# rekick2015-Prototyp.net
KiCad netlist of a schematic drawn in EAGLE
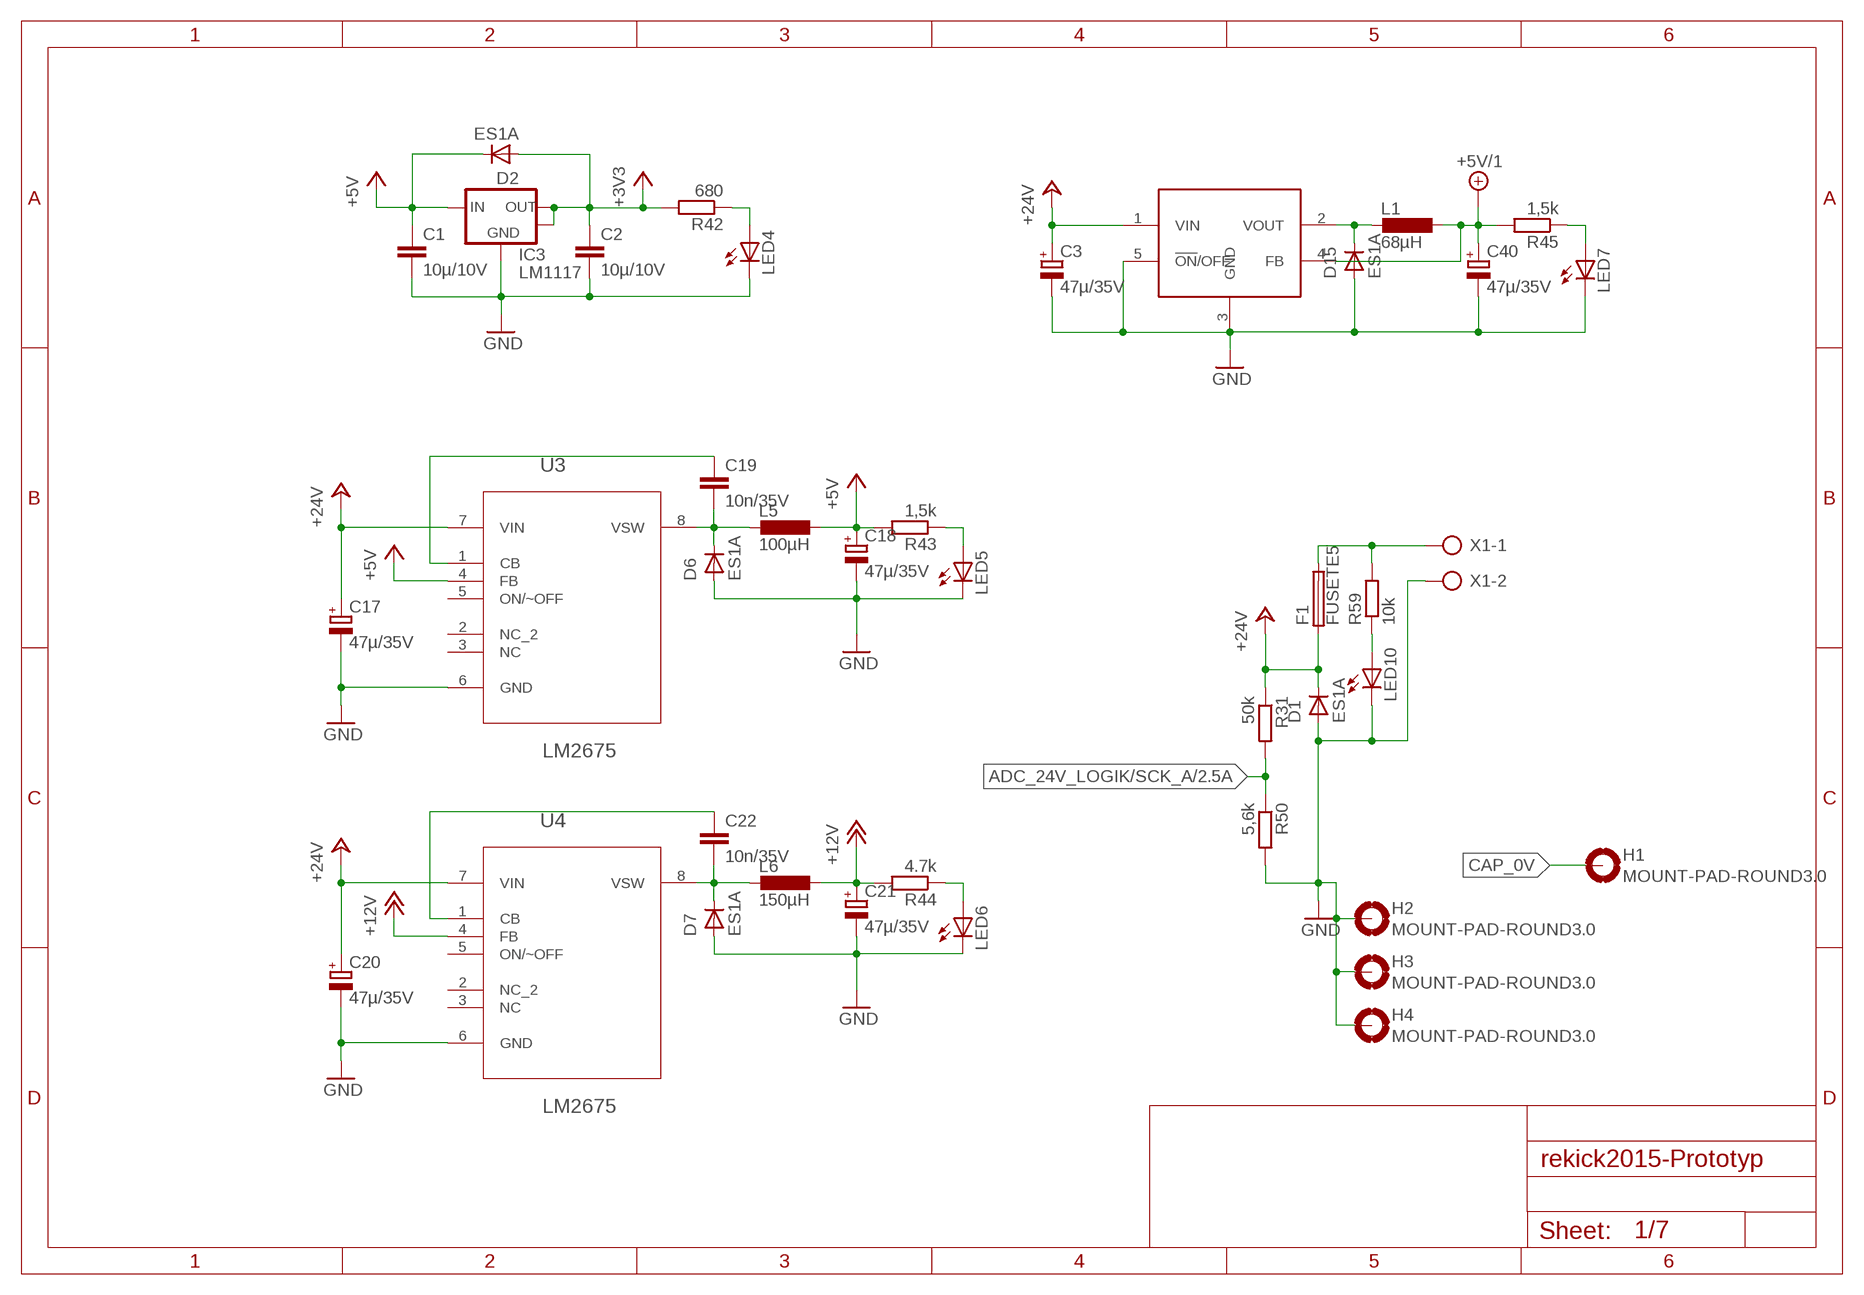
[diagram p0: schematic, sheet 1]
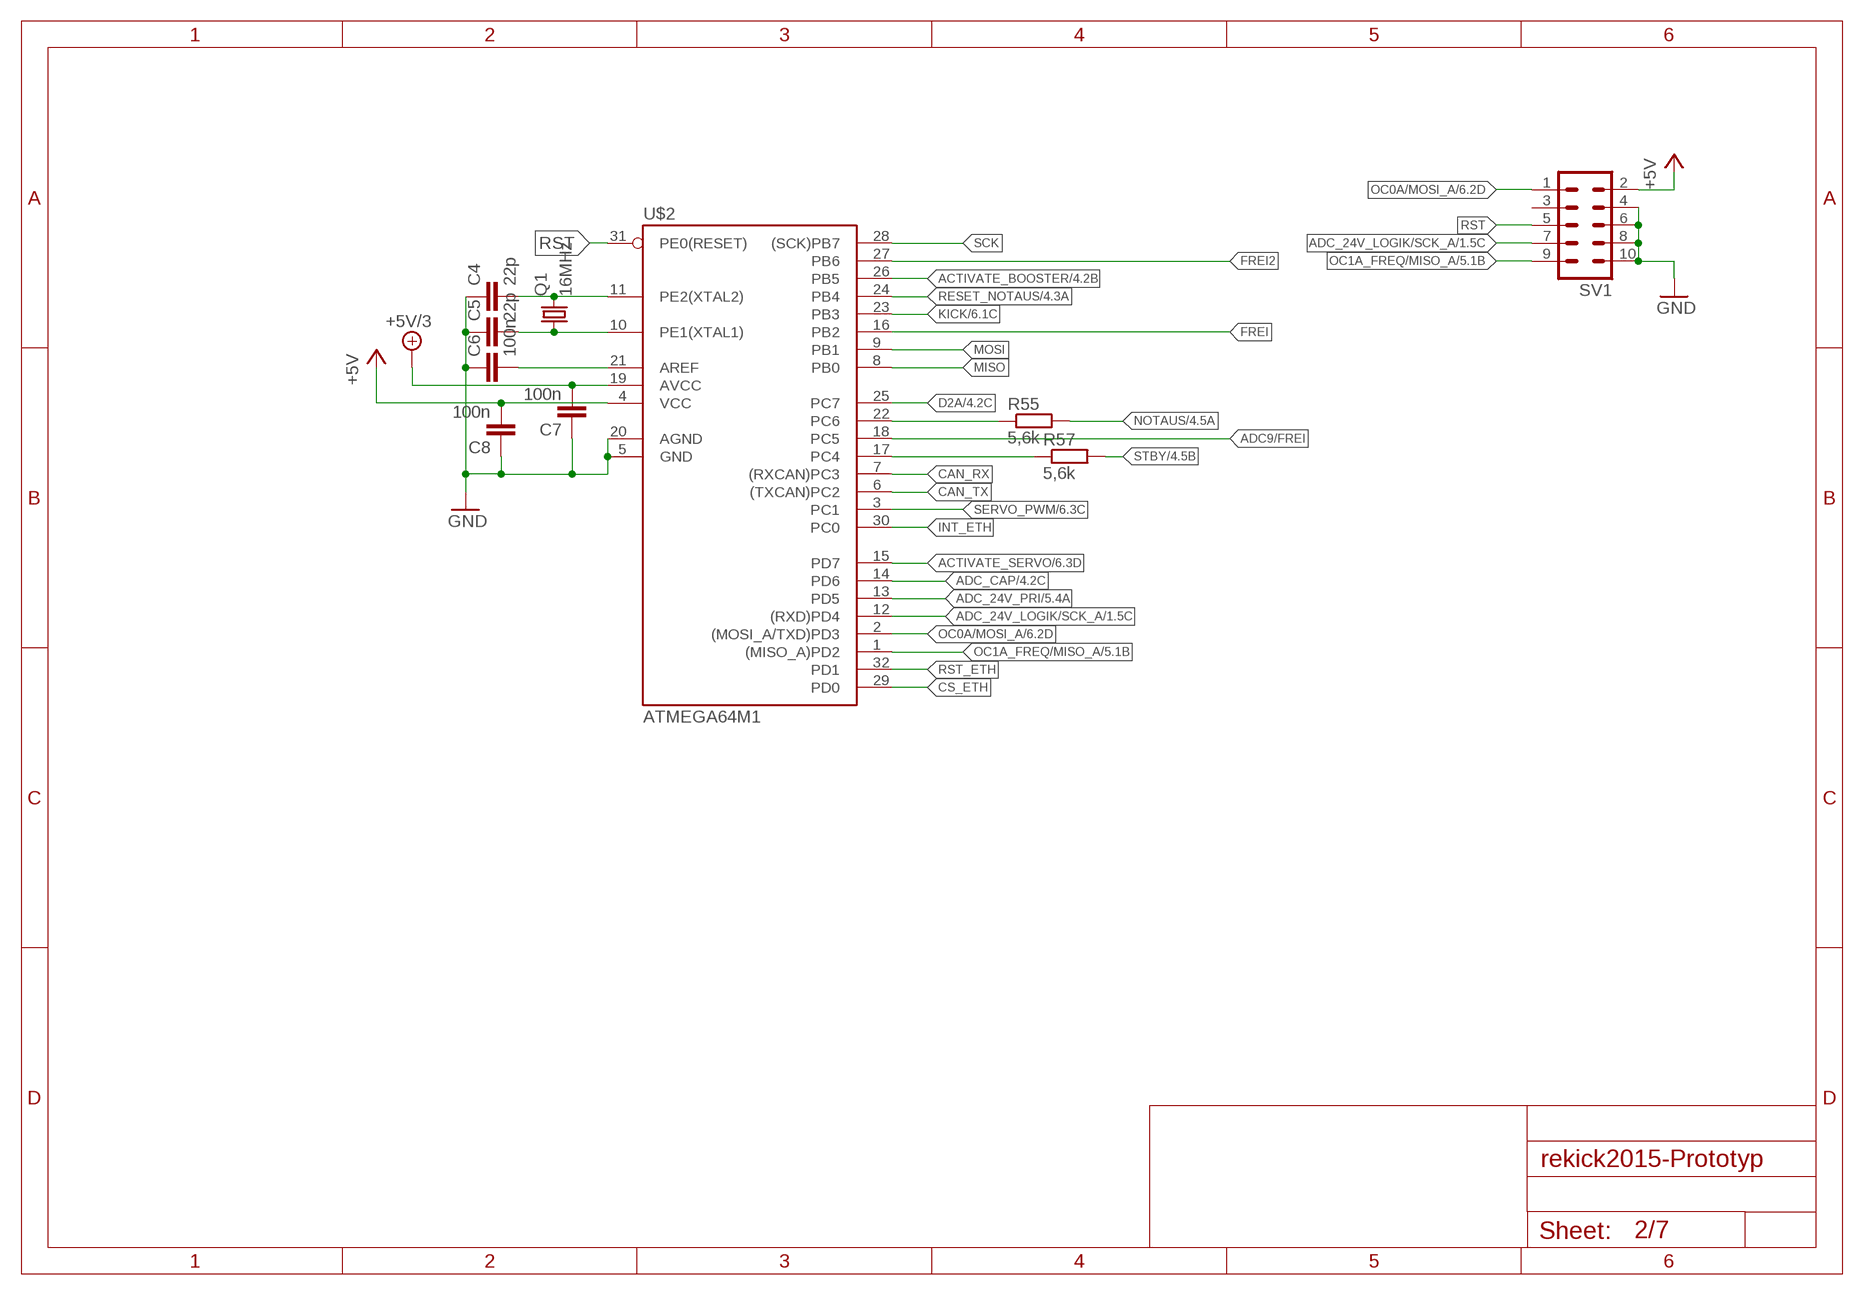
[diagram p1: schematic, sheet 2]
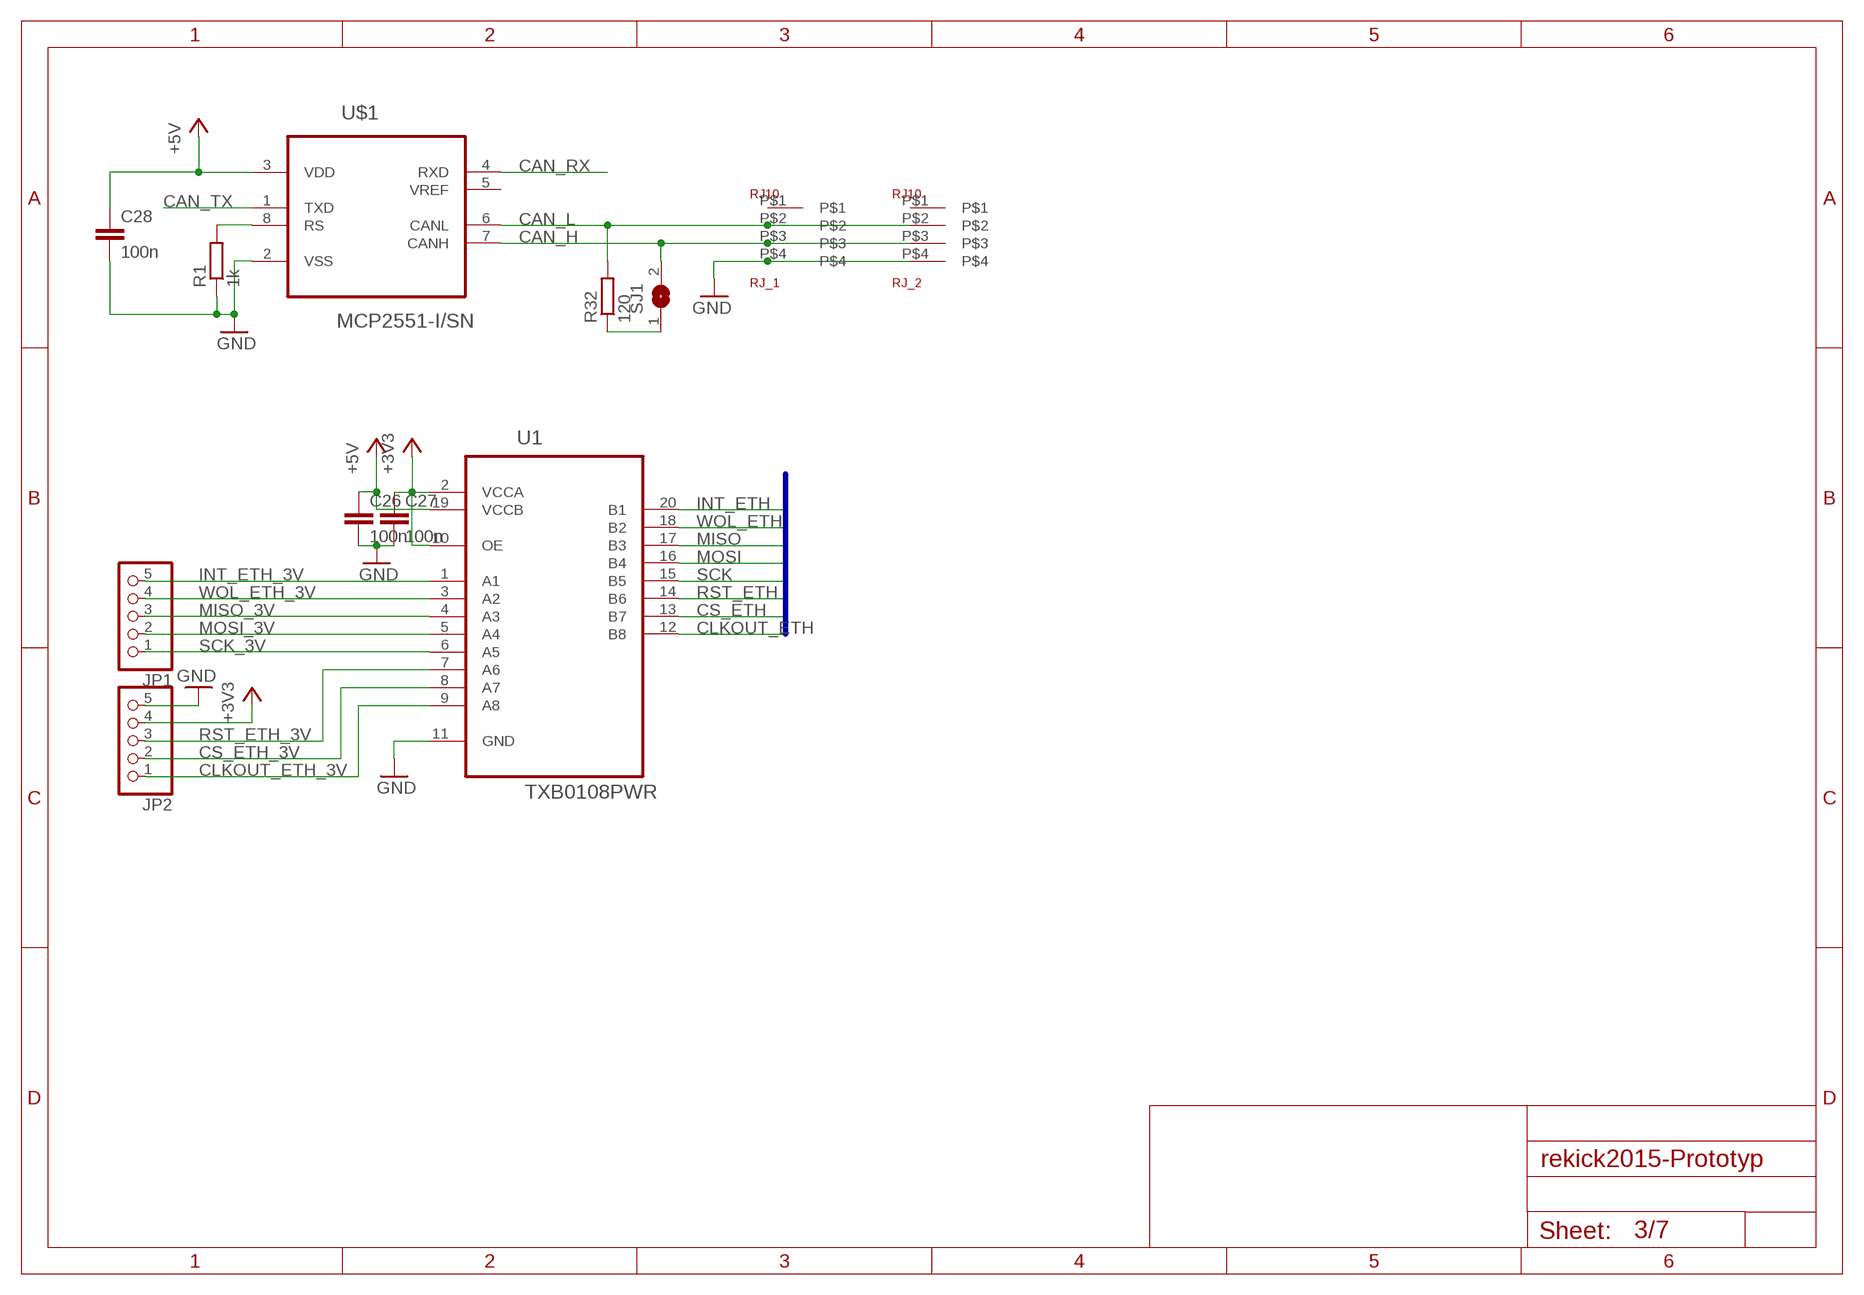
[diagram p2: schematic, sheet 3]
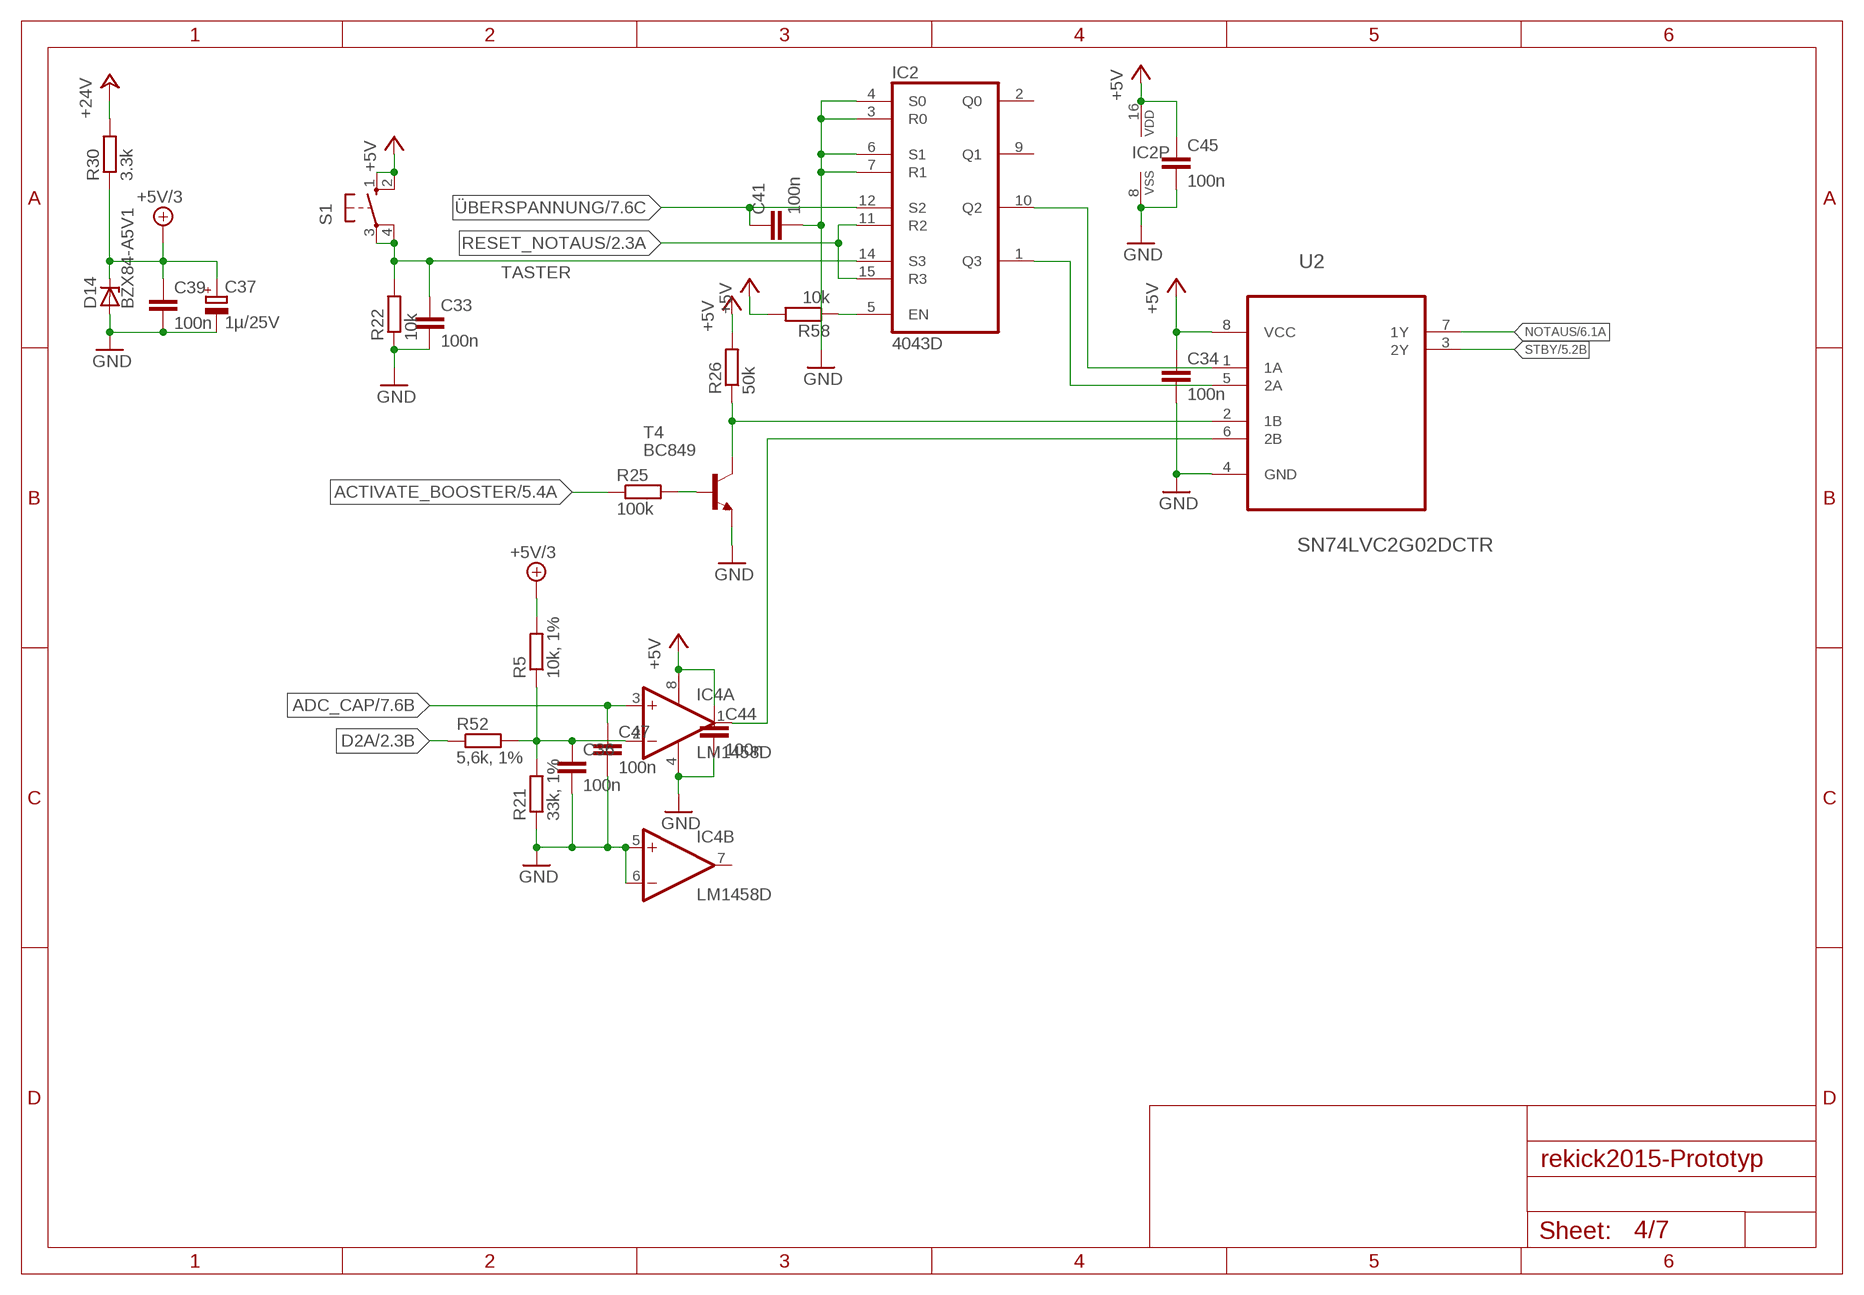
[diagram p3: schematic, sheet 4]
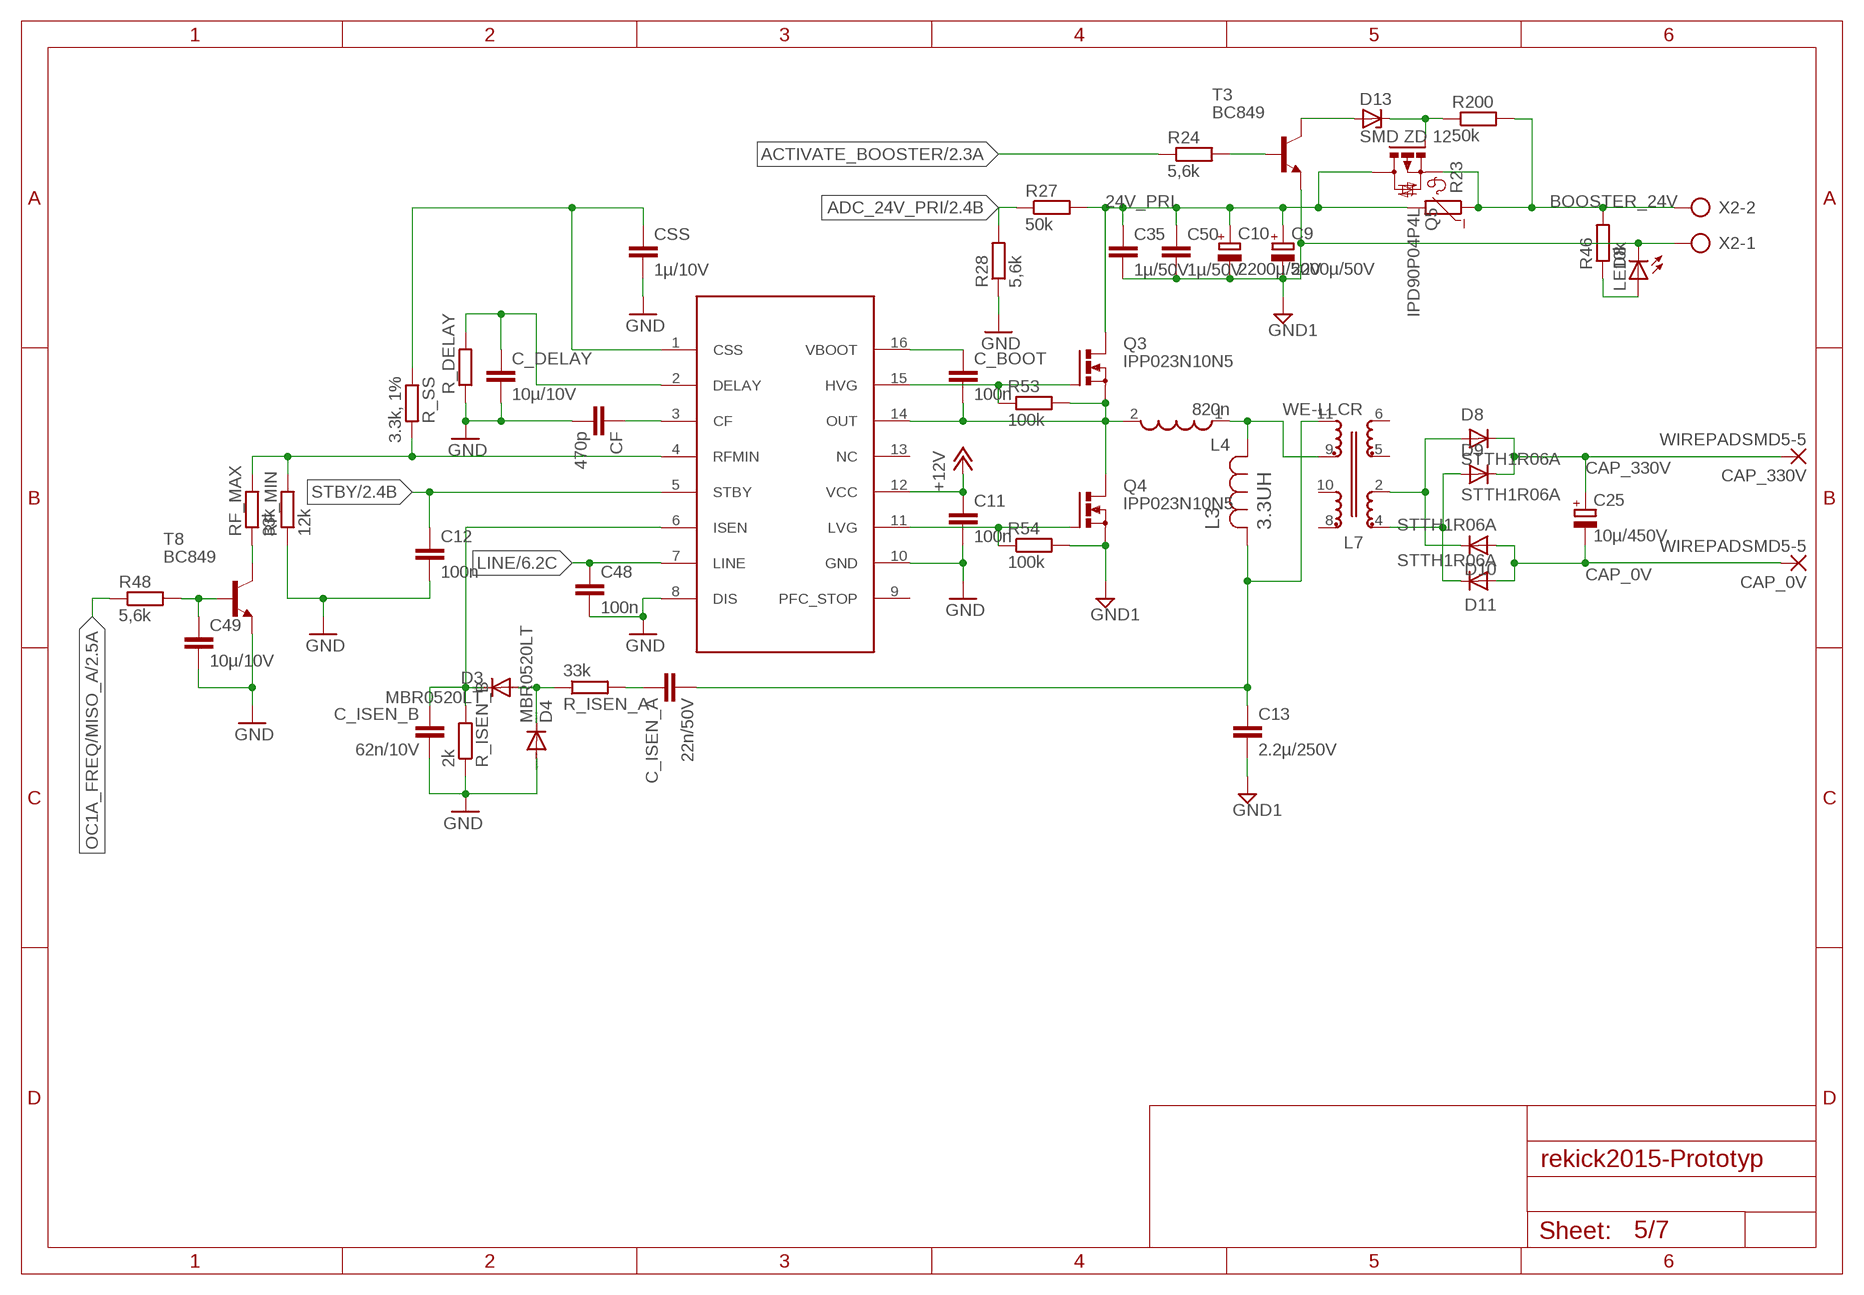
[diagram p4: schematic, sheet 5]
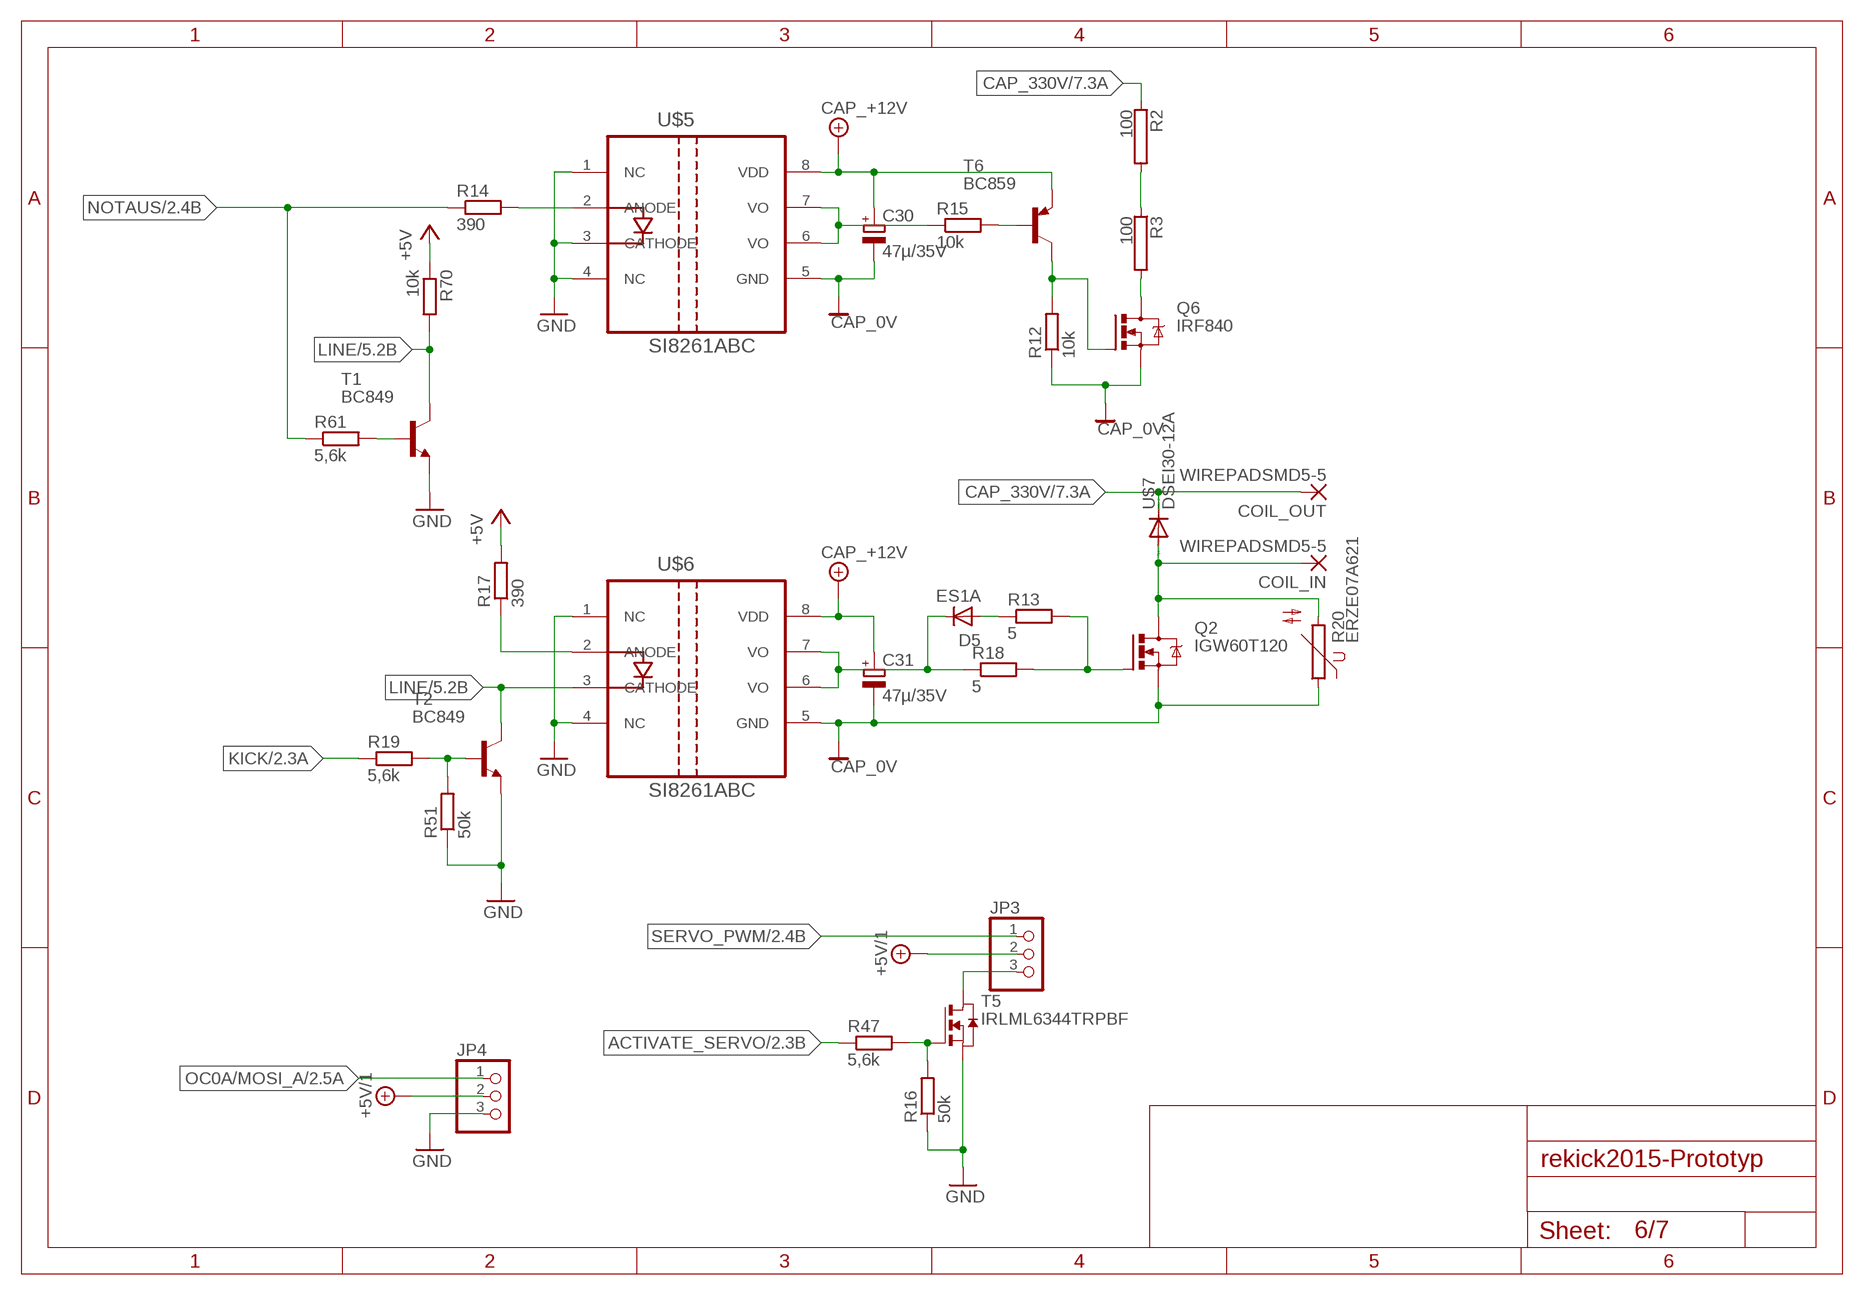
[diagram p5: schematic, sheet 6]
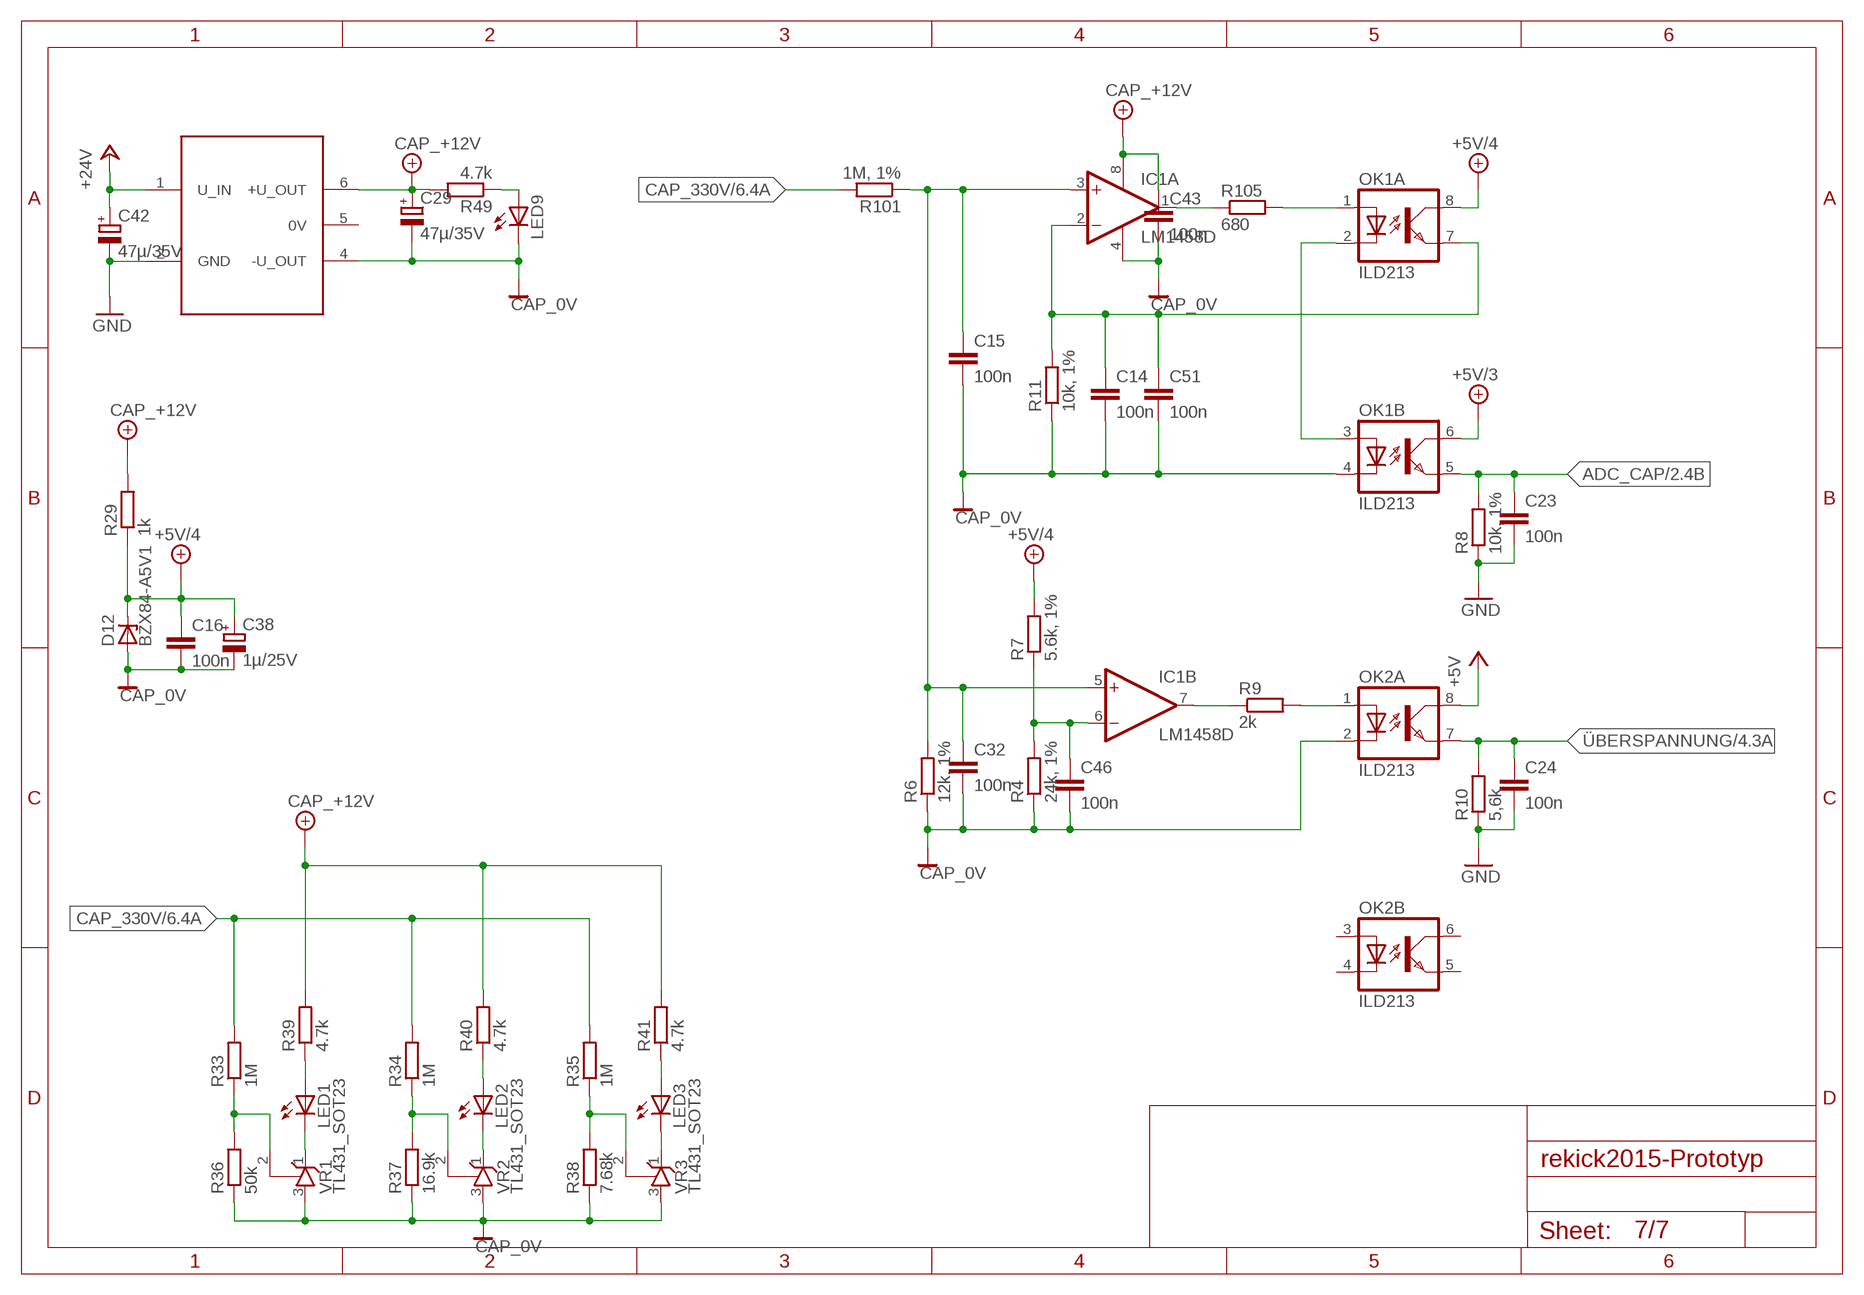
[diagram p6: schematic, sheet 7]

(export (version "E")
  (design (tool "Eeschema 10.0.6"))
  (components
    (comp (ref "C30")
      (value "47µ/35V")
      (footprint "eagle-import:E2-5")
      (libsource (lib "eagle-import") (part "CPOL-EUE2-5"))
    )
    (comp (ref "C31")
      (value "47µ/35V")
      (footprint "eagle-import:E2-5")
      (libsource (lib "eagle-import") (part "CPOL-EUE2-5"))
    )
    (comp (ref "COIL_IN")
      (value "WIREPADSMD5-5")
      (footprint "eagle-import:5-5")
      (libsource (lib "eagle-import") (part "WIREPADSMD5-5"))
    )
    (comp (ref "COIL_OUT")
      (value "WIREPADSMD5-5")
      (footprint "eagle-import:5-5")
      (libsource (lib "eagle-import") (part "WIREPADSMD5-5"))
    )
    (comp (ref "D5")
      (value "ES1A")
      (footprint "eagle-import:SMA-DO214AC")
      (libsource (lib "eagle-import") (part "GF1"))
    )
    (comp (ref "JP3")
      (value "PINHD-1X3")
      (footprint "eagle-import:1X03")
      (libsource (lib "eagle-import") (part "PINHD-1X3"))
    )
    (comp (ref "JP4")
      (value "PINHD-1X3")
      (footprint "eagle-import:1X03")
      (libsource (lib "eagle-import") (part "PINHD-1X3"))
    )
    (comp (ref "Q2")
      (value "IGW60T120")
      (footprint "eagle-import:TO247BV")
      (libsource (lib "eagle-import") (part "IRFPC40"))
    )
    (comp (ref "Q6")
      (value "IRF840")
      (footprint "eagle-import:TO220BV")
      (libsource (lib "eagle-import") (part "IRF740"))
    )
    (comp (ref "R2")
      (value "100")
      (footprint "eagle-import:HS25")
      (libsource (lib "eagle-import") (part "RHS25"))
    )
    (comp (ref "R3")
      (value "100")
      (footprint "eagle-import:HS25")
      (libsource (lib "eagle-import") (part "RHS25"))
    )
    (comp (ref "R12")
      (value "10k")
      (footprint "eagle-import:R0805")
      (libsource (lib "eagle-import") (part "R-EU_R0805"))
    )
    (comp (ref "R13")
      (value "5")
      (footprint "eagle-import:R2512")
      (libsource (lib "eagle-import") (part "R-EU_R2512"))
    )
    (comp (ref "R14")
      (value "390")
      (footprint "eagle-import:R0805")
      (libsource (lib "eagle-import") (part "R-EU_R0805"))
    )
    (comp (ref "R15")
      (value "10k")
      (footprint "eagle-import:R0805")
      (libsource (lib "eagle-import") (part "R-EU_R0805"))
    )
    (comp (ref "R16")
      (value "50k")
      (footprint "eagle-import:R0805")
      (libsource (lib "eagle-import") (part "R-EU_R0805"))
    )
    (comp (ref "R17")
      (value "390")
      (footprint "eagle-import:R0805")
      (libsource (lib "eagle-import") (part "R-EU_R0805"))
    )
    (comp (ref "R18")
      (value "5")
      (footprint "eagle-import:R2512")
      (libsource (lib "eagle-import") (part "R-EU_R2512"))
    )
    (comp (ref "R19")
      (value "5,6k")
      (footprint "eagle-import:R0805")
      (libsource (lib "eagle-import") (part "R-EU_R0805"))
    )
    (comp (ref "R20")
      (value "ERZE07A621")
      (footprint "eagle-import:S10K385")
      (libsource (lib "eagle-import") (part "S10K385"))
    )
    (comp (ref "R47")
      (value "5,6k")
      (footprint "eagle-import:R0805")
      (libsource (lib "eagle-import") (part "R-EU_R0805"))
    )
    (comp (ref "R51")
      (value "50k")
      (footprint "eagle-import:R0805")
      (libsource (lib "eagle-import") (part "R-EU_R0805"))
    )
    (comp (ref "R61")
      (value "5,6k")
      (footprint "eagle-import:R0805")
      (libsource (lib "eagle-import") (part "R-EU_R0805"))
    )
    (comp (ref "R70")
      (value "10k")
      (footprint "eagle-import:R0805")
      (libsource (lib "eagle-import") (part "R-EU_R0805"))
    )
    (comp (ref "T1")
      (value "BC849")
      (footprint "eagle-import:SOT23")
      (libsource (lib "eagle-import") (part "BC849"))
    )
    (comp (ref "T2")
      (value "BC849")
      (footprint "eagle-import:SOT23")
      (libsource (lib "eagle-import") (part "BC849"))
    )
    (comp (ref "T5")
      (value "IRLML6344TRPBF")
      (footprint "eagle-import:SOT-23")
      (libsource (lib "eagle-import") (part "NMOSSOT23"))
    )
    (comp (ref "T6")
      (value "BC859")
      (footprint "eagle-import:SOT23-BEC")
      (libsource (lib "eagle-import") (part "-PNP-SOT23-BECBC858C"))
    )
    (comp (ref "U$5")
      (value "SI8261ABC")
      (footprint "eagle-import:SOIC-8")
      (libsource (lib "eagle-import") (part "SI8261ABC"))
    )
    (comp (ref "U$6")
      (value "SI8261ABC")
      (footprint "eagle-import:SOIC-8")
      (libsource (lib "eagle-import") (part "SI8261ABC"))
    )
    (comp (ref "U$7")
      (value "DSEI30-12A")
      (footprint "eagle-import:TO247AD")
      (libsource (lib "eagle-import") (part "DSEI30-12A"))
    )
    (comp (ref "C33")
      (value "100n")
      (footprint "eagle-import:C0603")
      (libsource (lib "eagle-import") (part "C-EUC0603"))
    )
    (comp (ref "C34")
      (value "100n")
      (footprint "eagle-import:C0603")
      (libsource (lib "eagle-import") (part "C-EUC0603"))
    )
    (comp (ref "C36")
      (value "100n")
      (footprint "eagle-import:C0603")
      (libsource (lib "eagle-import") (part "C-EUC0603"))
    )
    (comp (ref "C37")
      (value "1µ/25V")
      (footprint "eagle-import:SMC_A")
      (libsource (lib "eagle-import") (part "CPOL-EUSMCA"))
    )
    (comp (ref "C39")
      (value "100n")
      (footprint "eagle-import:C0603")
      (libsource (lib "eagle-import") (part "C-EUC0603"))
    )
    (comp (ref "C41")
      (value "100n")
      (footprint "eagle-import:C0603")
      (libsource (lib "eagle-import") (part "C-EUC0603"))
    )
    (comp (ref "C44")
      (value "100n")
      (footprint "eagle-import:C0603")
      (libsource (lib "eagle-import") (part "C-EUC0603"))
    )
    (comp (ref "C45")
      (value "100n")
      (footprint "eagle-import:C0603")
      (libsource (lib "eagle-import") (part "C-EUC0603"))
    )
    (comp (ref "C47")
      (value "100n")
      (footprint "eagle-import:C0603")
      (libsource (lib "eagle-import") (part "C-EUC0603"))
    )
    (comp (ref "D14")
      (value "BZX84-A5V1")
      (footprint "eagle-import:TO236")
      (libsource (lib "eagle-import") (part "BZX84CSMD"))
    )
    (comp (ref "IC2")
      (value "4043D")
      (footprint "eagle-import:SO16")
      (libsource (lib "eagle-import") (part "4043D"))
    )
    (comp (ref "IC4")
      (value "LM1458D")
      (footprint "eagle-import:SO08")
      (libsource (lib "eagle-import") (part "1458DLM"))
    )
    (comp (ref "R5")
      (value "10k, 1%")
      (footprint "eagle-import:R0805")
      (libsource (lib "eagle-import") (part "R-EU_R0805"))
    )
    (comp (ref "R21")
      (value "33k, 1%")
      (footprint "eagle-import:R0805")
      (libsource (lib "eagle-import") (part "R-EU_R0805"))
    )
    (comp (ref "R22")
      (value "10k")
      (footprint "eagle-import:R0805")
      (libsource (lib "eagle-import") (part "R-EU_R0805"))
    )
    (comp (ref "R25")
      (value "100k")
      (footprint "eagle-import:R0805")
      (libsource (lib "eagle-import") (part "R-EU_R0805"))
    )
    (comp (ref "R26")
      (value "50k")
      (footprint "eagle-import:R0805")
      (libsource (lib "eagle-import") (part "R-EU_R0805"))
    )
    (comp (ref "R30")
      (value "3.3k")
      (footprint "eagle-import:R0805")
      (libsource (lib "eagle-import") (part "R-EU_R0805"))
    )
    (comp (ref "R52")
      (value "5,6k, 1%")
      (footprint "eagle-import:R0805")
      (libsource (lib "eagle-import") (part "R-EU_R0805"))
    )
    (comp (ref "R58")
      (value "10k")
      (footprint "eagle-import:R0805")
      (libsource (lib "eagle-import") (part "R-EU_R0805"))
    )
    (comp (ref "S1")
      (value "10-XX")
      (footprint "eagle-import:B3F-10XX")
      (libsource (lib "eagle-import") (part "10-XX"))
    )
    (comp (ref "T4")
      (value "BC849")
      (footprint "eagle-import:SOT23")
      (libsource (lib "eagle-import") (part "BC849"))
    )
    (comp (ref "U2")
      (value "SN74LVC2G02DCTR")
      (footprint "eagle-import:SOP65P400X130-8N")
      (libsource (lib "eagle-import") (part "SN74LVC2G02DCTR"))
    )
    (comp (ref "C9")
      (value "2200µ/50V")
      (footprint "eagle-import:E5-13")
      (libsource (lib "eagle-import") (part "CPOL-EUE5-13"))
    )
    (comp (ref "C10")
      (value "2200µ/50V")
      (footprint "eagle-import:E5-13")
      (libsource (lib "eagle-import") (part "CPOL-EUE5-13"))
    )
    (comp (ref "C11")
      (value "100n")
      (footprint "eagle-import:C0603")
      (libsource (lib "eagle-import") (part "C-EUC0603"))
    )
    (comp (ref "C12")
      (value "100n")
      (footprint "eagle-import:C0603")
      (libsource (lib "eagle-import") (part "C-EUC0603"))
    )
    (comp (ref "C13")
      (value "2.2µ/250V")
      (footprint "eagle-import:C2220K")
      (libsource (lib "eagle-import") (part "C-EUC2220K"))
    )
    (comp (ref "C25")
      (value "10µ/450V")
      (footprint "eagle-import:E5-10,5")
      (libsource (lib "eagle-import") (part "CPOL-EUE5-10.5"))
    )
    (comp (ref "C35")
      (value "1µ/50V")
      (footprint "eagle-import:C1206")
      (libsource (lib "eagle-import") (part "C-EUC1206"))
    )
    (comp (ref "C48")
      (value "100n")
      (footprint "eagle-import:C0603")
      (libsource (lib "eagle-import") (part "C-EUC0603"))
    )
    (comp (ref "C49")
      (value "10µ/10V")
      (footprint "eagle-import:C0603")
      (libsource (lib "eagle-import") (part "C-EUC0603"))
    )
    (comp (ref "C50")
      (value "1µ/50V")
      (footprint "eagle-import:C1206")
      (libsource (lib "eagle-import") (part "C-EUC1206"))
    )
    (comp (ref "CAP_0V")
      (value "WIREPADSMD5-5")
      (footprint "eagle-import:5-5")
      (libsource (lib "eagle-import") (part "WIREPADSMD5-5"))
    )
    (comp (ref "CAP_330V")
      (value "WIREPADSMD5-5")
      (footprint "eagle-import:5-5")
      (libsource (lib "eagle-import") (part "WIREPADSMD5-5"))
    )
    (comp (ref "CF")
      (value "470p")
      (footprint "eagle-import:C0603")
      (libsource (lib "eagle-import") (part "C-EUC0603"))
    )
    (comp (ref "CSS")
      (value "1µ/10V")
      (footprint "eagle-import:C0603")
      (libsource (lib "eagle-import") (part "C-EUC0603"))
    )
    (comp (ref "C_BOOT")
      (value "100n")
      (footprint "eagle-import:C0603")
      (libsource (lib "eagle-import") (part "C-EUC0603"))
    )
    (comp (ref "C_DELAY")
      (value "10µ/10V")
      (footprint "eagle-import:C0603")
      (libsource (lib "eagle-import") (part "C-EUC0603"))
    )
    (comp (ref "C_ISEN_A")
      (value "22n/50V")
      (footprint "eagle-import:C0603")
      (libsource (lib "eagle-import") (part "C-EUC0603"))
    )
    (comp (ref "C_ISEN_B")
      (value "62n/10V")
      (footprint "eagle-import:C0603")
      (libsource (lib "eagle-import") (part "C-EUC0603"))
    )
    (comp (ref "D3")
      (value "MBR0520LT")
      (footprint "eagle-import:SOD123")
      (libsource (lib "eagle-import") (part "MBR0520LT"))
    )
    (comp (ref "D4")
      (value "MBR0520LT")
      (footprint "eagle-import:SOD123")
      (libsource (lib "eagle-import") (part "MBR0520LT"))
    )
    (comp (ref "D8")
      (value "STTH1R06A")
      (footprint "eagle-import:SMA-DO214AC")
      (libsource (lib "eagle-import") (part "GF1"))
    )
    (comp (ref "D9")
      (value "STTH1R06A")
      (footprint "eagle-import:SMA-DO214AC")
      (libsource (lib "eagle-import") (part "GF1"))
    )
    (comp (ref "D10")
      (value "STTH1R06A")
      (footprint "eagle-import:SMA-DO214AC")
      (libsource (lib "eagle-import") (part "GF1"))
    )
    (comp (ref "D11")
      (value "STTH1R06A")
      (footprint "eagle-import:SMA-DO214AC")
      (libsource (lib "eagle-import") (part "GF1"))
    )
    (comp (ref "D13")
      (value "SMD ZD 12")
      (footprint "eagle-import:TO236")
      (libsource (lib "eagle-import") (part "BZX84CSMD"))
    )
    (comp (ref "L3")
      (value "3.3UH")
      (footprint "eagle-import:IND_ELLATP-B")
      (fields (field (name "MPN") "ELLATP3R3NB"))
      (libsource (lib "eagle-import") (part "ELL-ATP-BATP3R3NB"))
    )
    (comp (ref "L4")
      (value "820n")
      (footprint "eagle-import:WE-HCI_1890")
      (libsource (lib "eagle-import") (part "WE-HCI_1890"))
    )
    (comp (ref "L7")
      (value "WE-LLCR")
      (footprint "eagle-import:WE-LLCR_ETD34")
      (libsource (lib "eagle-import") (part "WE-LLCR_ETD34"))
    )
    (comp (ref "LED8")
      (value "LEDCHIP-LED0805")
      (footprint "eagle-import:CHIP-LED0805")
      (libsource (lib "eagle-import") (part "LEDCHIP-LED0805"))
    )
    (comp (ref "Q3")
      (value "IPP023N10N5")
      (footprint "eagle-import:TO220BV")
      (libsource (lib "eagle-import") (part "PMOSFET_NTO220BV"))
    )
    (comp (ref "Q4")
      (value "IPP023N10N5")
      (footprint "eagle-import:TO220BV")
      (libsource (lib "eagle-import") (part "PMOSFET_NTO220BV"))
    )
    (comp (ref "Q5")
      (value "IPD90P04P4L")
      (footprint "eagle-import:D-PAK_TO252AA")
      (libsource (lib "eagle-import") (part "IRF?5305R"))
    )
    (comp (ref "R23")
      (value "NTC644A")
      (footprint "eagle-import:N644A")
      (libsource (lib "eagle-import") (part "NTC644A"))
    )
    (comp (ref "R24")
      (value "5,6k")
      (footprint "eagle-import:R0805")
      (libsource (lib "eagle-import") (part "R-EU_R0805"))
    )
    (comp (ref "R27")
      (value "50k")
      (footprint "eagle-import:R0805")
      (libsource (lib "eagle-import") (part "R-EU_R0805"))
    )
    (comp (ref "R28")
      (value "5,6k")
      (footprint "eagle-import:R0805")
      (libsource (lib "eagle-import") (part "R-EU_R0805"))
    )
    (comp (ref "R46")
      (value "10k")
      (footprint "eagle-import:R0805")
      (libsource (lib "eagle-import") (part "R-EU_R0805"))
    )
    (comp (ref "R48")
      (value "5,6k")
      (footprint "eagle-import:R0805")
      (libsource (lib "eagle-import") (part "R-EU_R0805"))
    )
    (comp (ref "R53")
      (value "100k")
      (footprint "eagle-import:R0805")
      (libsource (lib "eagle-import") (part "R-EU_R0805"))
    )
    (comp (ref "R54")
      (value "100k")
      (footprint "eagle-import:R0805")
      (libsource (lib "eagle-import") (part "R-EU_R0805"))
    )
    (comp (ref "R200")
      (value "50k")
      (footprint "eagle-import:R0805")
      (libsource (lib "eagle-import") (part "R-EU_R0805"))
    )
    (comp (ref "RF_MAX")
      (value "33k")
      (footprint "eagle-import:R0805")
      (libsource (lib "eagle-import") (part "R-EU_R0805"))
    )
    (comp (ref "RF_MIN")
      (value "12k")
      (footprint "eagle-import:R0805")
      (libsource (lib "eagle-import") (part "R-EU_R0805"))
    )
    (comp (ref "R_DELAY")
      (value "R-EU_R0805")
      (footprint "eagle-import:R0805")
      (libsource (lib "eagle-import") (part "R-EU_R0805"))
    )
    (comp (ref "R_ISEN_A")
      (value "33k")
      (footprint "eagle-import:R0805")
      (libsource (lib "eagle-import") (part "R-EU_R0805"))
    )
    (comp (ref "R_ISEN_B")
      (value "2k")
      (footprint "eagle-import:R0805")
      (libsource (lib "eagle-import") (part "R-EU_R0805"))
    )
    (comp (ref "R_SS")
      (value "3.3k, 1%")
      (footprint "eagle-import:R0805")
      (libsource (lib "eagle-import") (part "R-EU_R0805"))
    )
    (comp (ref "T3")
      (value "BC849")
      (footprint "eagle-import:SOT23")
      (libsource (lib "eagle-import") (part "BC849"))
    )
    (comp (ref "T8")
      (value "BC849")
      (footprint "eagle-import:SOT23")
      (libsource (lib "eagle-import") (part "BC849"))
    )
    (comp (ref "U$3")
      (value "L6599")
      (footprint "eagle-import:SO16")
      (libsource (lib "eagle-import") (part "L6599"))
    )
    (comp (ref "X2")
      (value "AK500/2-H")
      (footprint "eagle-import:AK500_2-H")
      (libsource (lib "eagle-import") (part "AK500/2-H"))
    )
    (comp (ref "C4")
      (value "22p")
      (footprint "eagle-import:C0603")
      (libsource (lib "eagle-import") (part "C-EUC0603"))
    )
    (comp (ref "C5")
      (value "22p")
      (footprint "eagle-import:C0603")
      (libsource (lib "eagle-import") (part "C-EUC0603"))
    )
    (comp (ref "C6")
      (value "100n")
      (footprint "eagle-import:C0603")
      (libsource (lib "eagle-import") (part "C-EUC0603"))
    )
    (comp (ref "C7")
      (value "100n")
      (footprint "eagle-import:C0603")
      (libsource (lib "eagle-import") (part "C-EUC0603"))
    )
    (comp (ref "C8")
      (value "100n")
      (footprint "eagle-import:C0603")
      (libsource (lib "eagle-import") (part "C-EUC0603"))
    )
    (comp (ref "Q1")
      (value "16MHz")
      (footprint "eagle-import:HC49UP")
      (libsource (lib "eagle-import") (part "CRYSTALHC49UP"))
    )
    (comp (ref "R55")
      (value "5,6k")
      (footprint "eagle-import:R0805")
      (libsource (lib "eagle-import") (part "R-EU_R0805"))
    )
    (comp (ref "R57")
      (value "5,6k")
      (footprint "eagle-import:R0805")
      (libsource (lib "eagle-import") (part "R-EU_R0805"))
    )
    (comp (ref "SV1")
      (value "ML10")
      (footprint "eagle-import:ML10")
      (libsource (lib "eagle-import") (part "ML10"))
    )
    (comp (ref "U$2")
      (value "ATMEGA64M1")
      (footprint "eagle-import:TQFP32-08")
      (libsource (lib "eagle-import") (part "ATMEGA64M1"))
    )
    (comp (ref "C1")
      (value "10µ/10V")
      (footprint "eagle-import:C0603")
      (libsource (lib "eagle-import") (part "C-EUC0603"))
    )
    (comp (ref "C2")
      (value "10µ/10V")
      (footprint "eagle-import:C0603")
      (libsource (lib "eagle-import") (part "C-EUC0603"))
    )
    (comp (ref "C3")
      (value "47µ/35V")
      (footprint "eagle-import:PANASONIC_D")
      (libsource (lib "eagle-import") (part "CPOL-EUD"))
    )
    (comp (ref "C17")
      (value "47µ/35V")
      (footprint "eagle-import:PANASONIC_D")
      (libsource (lib "eagle-import") (part "CPOL-EUD"))
    )
    (comp (ref "C18")
      (value "47µ/35V")
      (footprint "eagle-import:PANASONIC_D")
      (libsource (lib "eagle-import") (part "CPOL-EUD"))
    )
    (comp (ref "C19")
      (value "10n/35V")
      (footprint "eagle-import:C0603")
      (libsource (lib "eagle-import") (part "C-EUC0603"))
    )
    (comp (ref "C20")
      (value "47µ/35V")
      (footprint "eagle-import:PANASONIC_D")
      (libsource (lib "eagle-import") (part "CPOL-EUD"))
    )
    (comp (ref "C21")
      (value "47µ/35V")
      (footprint "eagle-import:PANASONIC_D")
      (libsource (lib "eagle-import") (part "CPOL-EUD"))
    )
    (comp (ref "C22")
      (value "10n/35V")
      (footprint "eagle-import:C0603")
      (libsource (lib "eagle-import") (part "C-EUC0603"))
    )
    (comp (ref "C40")
      (value "47µ/35V")
      (footprint "eagle-import:PANASONIC_D")
      (libsource (lib "eagle-import") (part "CPOL-EUD"))
    )
    (comp (ref "D1")
      (value "ES1A")
      (footprint "eagle-import:SMA-DO214AC")
      (libsource (lib "eagle-import") (part "GF1"))
    )
    (comp (ref "D2")
      (value "ES1A")
      (footprint "eagle-import:SMA-DO214AC")
      (libsource (lib "eagle-import") (part "GF1"))
    )
    (comp (ref "D6")
      (value "ES1A")
      (footprint "eagle-import:SMA-DO214AC")
      (libsource (lib "eagle-import") (part "GF1"))
    )
    (comp (ref "D7")
      (value "ES1A")
      (footprint "eagle-import:SMA-DO214AC")
      (libsource (lib "eagle-import") (part "GF1"))
    )
    (comp (ref "D15")
      (value "ES1A")
      (footprint "eagle-import:SMA-DO214AC")
      (libsource (lib "eagle-import") (part "GF1"))
    )
    (comp (ref "F1")
      (value "FUSETE5")
      (footprint "eagle-import:TE5")
      (libsource (lib "eagle-import") (part "FUSETE5"))
    )
    (comp (ref "H1")
      (value "MOUNT-PAD-ROUND3.0")
      (footprint "eagle-import:3,0-PAD")
      (libsource (lib "eagle-import") (part "MOUNT-PAD-ROUND3.0"))
    )
    (comp (ref "H2")
      (value "MOUNT-PAD-ROUND3.0")
      (footprint "eagle-import:3,0-PAD")
      (libsource (lib "eagle-import") (part "MOUNT-PAD-ROUND3.0"))
    )
    (comp (ref "H3")
      (value "MOUNT-PAD-ROUND3.0")
      (footprint "eagle-import:3,0-PAD")
      (libsource (lib "eagle-import") (part "MOUNT-PAD-ROUND3.0"))
    )
    (comp (ref "H4")
      (value "MOUNT-PAD-ROUND3.0")
      (footprint "eagle-import:3,0-PAD")
      (libsource (lib "eagle-import") (part "MOUNT-PAD-ROUND3.0"))
    )
    (comp (ref "IC3")
      (value "LM1117")
      (footprint "eagle-import:SOT223")
      (libsource (lib "eagle-import") (part "LM1117"))
    )
    (comp (ref "L1")
      (value "68µH")
      (footprint "eagle-import:PISM")
      (libsource (lib "eagle-import") (part "L-EUPISM"))
    )
    (comp (ref "L5")
      (value "100µH")
      (footprint "eagle-import:PISM")
      (libsource (lib "eagle-import") (part "L-EUPISM"))
    )
    (comp (ref "L6")
      (value "150µH")
      (footprint "eagle-import:PISM")
      (libsource (lib "eagle-import") (part "L-EUPISM"))
    )
    (comp (ref "LED4")
      (value "LEDCHIP-LED0805")
      (footprint "eagle-import:CHIP-LED0805")
      (libsource (lib "eagle-import") (part "LEDCHIP-LED0805"))
    )
    (comp (ref "LED5")
      (value "LEDCHIP-LED0805")
      (footprint "eagle-import:CHIP-LED0805")
      (libsource (lib "eagle-import") (part "LEDCHIP-LED0805"))
    )
    (comp (ref "LED6")
      (value "LEDCHIP-LED0805")
      (footprint "eagle-import:CHIP-LED0805")
      (libsource (lib "eagle-import") (part "LEDCHIP-LED0805"))
    )
    (comp (ref "LED7")
      (value "LEDCHIP-LED0805")
      (footprint "eagle-import:CHIP-LED0805")
      (libsource (lib "eagle-import") (part "LEDCHIP-LED0805"))
    )
    (comp (ref "LED10")
      (value "LEDCHIP-LED0805")
      (footprint "eagle-import:CHIP-LED0805")
      (libsource (lib "eagle-import") (part "LEDCHIP-LED0805"))
    )
    (comp (ref "R31")
      (value "50k")
      (footprint "eagle-import:R0805")
      (libsource (lib "eagle-import") (part "R-EU_R0805"))
    )
    (comp (ref "R42")
      (value "680")
      (footprint "eagle-import:R0805")
      (libsource (lib "eagle-import") (part "R-EU_R0805"))
    )
    (comp (ref "R43")
      (value "1,5k")
      (footprint "eagle-import:R0805")
      (libsource (lib "eagle-import") (part "R-EU_R0805"))
    )
    (comp (ref "R44")
      (value "4.7k")
      (footprint "eagle-import:R0805")
      (libsource (lib "eagle-import") (part "R-EU_R0805"))
    )
    (comp (ref "R45")
      (value "1,5k")
      (footprint "eagle-import:R0805")
      (libsource (lib "eagle-import") (part "R-EU_R0805"))
    )
    (comp (ref "R50")
      (value "5,6k")
      (footprint "eagle-import:R0805")
      (libsource (lib "eagle-import") (part "R-EU_R0805"))
    )
    (comp (ref "R59")
      (value "10k")
      (footprint "eagle-import:R0805")
      (libsource (lib "eagle-import") (part "R-EU_R0805"))
    )
    (comp (ref "U$8")
      (value "LM2576")
      (footprint "eagle-import:TO220511")
      (libsource (lib "eagle-import") (part "LM2576"))
    )
    (comp (ref "U3")
      (value "LM2675")
      (footprint "eagle-import:SOIC127P620X175-8N")
      (fields (field (name "MPN") "LM2675M-3.3"))
      (libsource (lib "eagle-import") (part "LM2675M-3.3"))
    )
    (comp (ref "U4")
      (value "LM2675")
      (footprint "eagle-import:SOIC127P620X175-8N")
      (fields (field (name "MPN") "LM2675M-3.3"))
      (libsource (lib "eagle-import") (part "LM2675M-3.3"))
    )
    (comp (ref "X1")
      (value "AK500/2-H")
      (footprint "eagle-import:AK500_2-H")
      (libsource (lib "eagle-import") (part "AK500/2-H"))
    )
    (comp (ref "C26")
      (value "100n")
      (footprint "eagle-import:C0603")
      (libsource (lib "eagle-import") (part "C-EUC0603"))
    )
    (comp (ref "C27")
      (value "100n")
      (footprint "eagle-import:C0603")
      (libsource (lib "eagle-import") (part "C-EUC0603"))
    )
    (comp (ref "C28")
      (value "100n")
      (footprint "eagle-import:C0603")
      (libsource (lib "eagle-import") (part "C-EUC0603"))
    )
    (comp (ref "JP1")
      (value "PINHD-1X5")
      (footprint "eagle-import:1X05")
      (libsource (lib "eagle-import") (part "PINHD-1X5"))
    )
    (comp (ref "JP2")
      (value "PINHD-1X5")
      (footprint "eagle-import:1X05")
      (libsource (lib "eagle-import") (part "PINHD-1X5"))
    )
    (comp (ref "R1")
      (value "1k")
      (footprint "eagle-import:R0805")
      (libsource (lib "eagle-import") (part "R-EU_R0805"))
    )
    (comp (ref "R32")
      (value "120")
      (footprint "eagle-import:R0805")
      (libsource (lib "eagle-import") (part "R-EU_R0805"))
    )
    (comp (ref "RJ_1")
      (value "RJ10")
      (footprint "eagle-import:RJ10")
      (libsource (lib "eagle-import") (part "RJ10"))
    )
    (comp (ref "RJ_2")
      (value "RJ10")
      (footprint "eagle-import:RJ10")
      (libsource (lib "eagle-import") (part "RJ10"))
    )
    (comp (ref "SJ1") (value "SJ") (footprint "eagle-import:SJ") (libsource (lib "eagle-import") (part "SJ")))
    (comp (ref "U$1")
      (value "MCP2551-I/SN")
      (footprint "eagle-import:SOIC127P600X175-8N")
      (libsource (lib "eagle-import") (part "MCP2551-I/SN"))
    )
    (comp (ref "U1")
      (value "TXB0108PWR")
      (footprint "eagle-import:SOP65P640X120-20N")
      (libsource (lib "eagle-import") (part "TXB0108PWR"))
    )
    (comp (ref "C14")
      (value "100n")
      (footprint "eagle-import:C0603")
      (libsource (lib "eagle-import") (part "C-EUC0603"))
    )
    (comp (ref "C15")
      (value "100n")
      (footprint "eagle-import:C0603")
      (libsource (lib "eagle-import") (part "C-EUC0603"))
    )
    (comp (ref "C16")
      (value "100n")
      (footprint "eagle-import:C0603")
      (libsource (lib "eagle-import") (part "C-EUC0603"))
    )
    (comp (ref "C23")
      (value "100n")
      (footprint "eagle-import:C0603")
      (libsource (lib "eagle-import") (part "C-EUC0603"))
    )
    (comp (ref "C24")
      (value "100n")
      (footprint "eagle-import:C0603")
      (libsource (lib "eagle-import") (part "C-EUC0603"))
    )
    (comp (ref "C29")
      (value "47µ/35V")
      (footprint "eagle-import:PANASONIC_D")
      (libsource (lib "eagle-import") (part "CPOL-EUD"))
    )
    (comp (ref "C32")
      (value "100n")
      (footprint "eagle-import:C0603")
      (libsource (lib "eagle-import") (part "C-EUC0603"))
    )
    (comp (ref "C38")
      (value "1µ/25V")
      (footprint "eagle-import:SMC_A")
      (libsource (lib "eagle-import") (part "CPOL-EUSMCA"))
    )
    (comp (ref "C42")
      (value "47µ/35V")
      (footprint "eagle-import:PANASONIC_D")
      (libsource (lib "eagle-import") (part "CPOL-EUD"))
    )
    (comp (ref "C43")
      (value "100n")
      (footprint "eagle-import:C0603")
      (libsource (lib "eagle-import") (part "C-EUC0603"))
    )
    (comp (ref "C46")
      (value "100n")
      (footprint "eagle-import:C0603")
      (libsource (lib "eagle-import") (part "C-EUC0603"))
    )
    (comp (ref "C51")
      (value "100n")
      (footprint "eagle-import:C0603")
      (libsource (lib "eagle-import") (part "C-EUC0603"))
    )
    (comp (ref "D12")
      (value "BZX84-A5V1")
      (footprint "eagle-import:TO236")
      (libsource (lib "eagle-import") (part "BZX84CSMD"))
    )
    (comp (ref "IC1")
      (value "LM1458D")
      (footprint "eagle-import:SO08")
      (libsource (lib "eagle-import") (part "1458DLM"))
    )
    (comp (ref "LED1")
      (value "LEDCHIP-LED0805")
      (footprint "eagle-import:CHIP-LED0805")
      (libsource (lib "eagle-import") (part "LEDCHIP-LED0805"))
    )
    (comp (ref "LED2")
      (value "LEDCHIP-LED0805")
      (footprint "eagle-import:CHIP-LED0805")
      (libsource (lib "eagle-import") (part "LEDCHIP-LED0805"))
    )
    (comp (ref "LED3")
      (value "LEDCHIP-LED0805")
      (footprint "eagle-import:CHIP-LED0805")
      (libsource (lib "eagle-import") (part "LEDCHIP-LED0805"))
    )
    (comp (ref "LED9")
      (value "LEDCHIP-LED0805")
      (footprint "eagle-import:CHIP-LED0805")
      (libsource (lib "eagle-import") (part "LEDCHIP-LED0805"))
    )
    (comp (ref "OK1")
      (value "ILD213")
      (footprint "eagle-import:SOIC08")
      (libsource (lib "eagle-import") (part "ILD213"))
    )
    (comp (ref "OK2")
      (value "ILD213")
      (footprint "eagle-import:SOIC08")
      (libsource (lib "eagle-import") (part "ILD213"))
    )
    (comp (ref "R4")
      (value "24k, 1%")
      (footprint "eagle-import:R0805")
      (libsource (lib "eagle-import") (part "R-EU_R0805"))
    )
    (comp (ref "R6")
      (value "12k, 1%")
      (footprint "eagle-import:R0805")
      (libsource (lib "eagle-import") (part "R-EU_R0805"))
    )
    (comp (ref "R7")
      (value "5.6k, 1%")
      (footprint "eagle-import:R0805")
      (libsource (lib "eagle-import") (part "R-EU_R0805"))
    )
    (comp (ref "R8")
      (value "10k, 1%")
      (footprint "eagle-import:R0805")
      (libsource (lib "eagle-import") (part "R-EU_R0805"))
    )
    (comp (ref "R9")
      (value "2k")
      (footprint "eagle-import:R0805")
      (libsource (lib "eagle-import") (part "R-EU_R0805"))
    )
    (comp (ref "R10")
      (value "5,6k")
      (footprint "eagle-import:R0805")
      (libsource (lib "eagle-import") (part "R-EU_R0805"))
    )
    (comp (ref "R11")
      (value "10k, 1%")
      (footprint "eagle-import:R0805")
      (libsource (lib "eagle-import") (part "R-EU_R0805"))
    )
    (comp (ref "R29")
      (value "1k")
      (footprint "eagle-import:R0805")
      (libsource (lib "eagle-import") (part "R-EU_R0805"))
    )
    (comp (ref "R33")
      (value "1M")
      (footprint "eagle-import:R2512")
      (libsource (lib "eagle-import") (part "R-EU_R2512"))
    )
    (comp (ref "R34")
      (value "1M")
      (footprint "eagle-import:R2512")
      (libsource (lib "eagle-import") (part "R-EU_R2512"))
    )
    (comp (ref "R35")
      (value "1M")
      (footprint "eagle-import:R2512")
      (libsource (lib "eagle-import") (part "R-EU_R2512"))
    )
    (comp (ref "R36")
      (value "50k")
      (footprint "eagle-import:R0805")
      (libsource (lib "eagle-import") (part "R-EU_R0805"))
    )
    (comp (ref "R37")
      (value "16.9k")
      (footprint "eagle-import:R0805")
      (libsource (lib "eagle-import") (part "R-EU_R0805"))
    )
    (comp (ref "R38")
      (value "7.68k")
      (footprint "eagle-import:R0805")
      (libsource (lib "eagle-import") (part "R-EU_R0805"))
    )
    (comp (ref "R39")
      (value "4.7k")
      (footprint "eagle-import:R0805")
      (libsource (lib "eagle-import") (part "R-EU_R0805"))
    )
    (comp (ref "R40")
      (value "4.7k")
      (footprint "eagle-import:R0805")
      (libsource (lib "eagle-import") (part "R-EU_R0805"))
    )
    (comp (ref "R41")
      (value "4.7k")
      (footprint "eagle-import:R0805")
      (libsource (lib "eagle-import") (part "R-EU_R0805"))
    )
    (comp (ref "R49")
      (value "4.7k")
      (footprint "eagle-import:R0805")
      (libsource (lib "eagle-import") (part "R-EU_R0805"))
    )
    (comp (ref "R101")
      (value "1M, 1%")
      (footprint "eagle-import:R2512")
      (libsource (lib "eagle-import") (part "R-EU_R2512"))
    )
    (comp (ref "R105")
      (value "680")
      (footprint "eagle-import:R0805")
      (libsource (lib "eagle-import") (part "R-EU_R0805"))
    )
    (comp (ref "U$4")
      (value "TMH-D")
      (footprint "eagle-import:TMH-D")
      (libsource (lib "eagle-import") (part "TMH-D"))
    )
    (comp (ref "VR1")
      (value "TL431_SOT23")
      (footprint "eagle-import:SOT23")
      (libsource (lib "eagle-import") (part "TL431_SOT23"))
    )
    (comp (ref "VR2")
      (value "TL431_SOT23")
      (footprint "eagle-import:SOT23")
      (libsource (lib "eagle-import") (part "TL431_SOT23"))
    )
    (comp (ref "VR3")
      (value "TL431_SOT23")
      (footprint "eagle-import:SOT23")
      (libsource (lib "eagle-import") (part "TL431_SOT23"))
    )
  )
  (nets
    (net (code "1") (name "+3V3") (class "Default")
      (node (ref "C2") (pin "1") (pinfunction "1_1") (pintype "passive"))
      (node (ref "C27") (pin "1") (pinfunction "1_1") (pintype "passive"))
      (node (ref "D2") (pin "A") (pinfunction "A_A") (pintype "passive"))
      (node (ref "IC3") (pin "2") (pinfunction "OUT_2") (pintype "passive"))
      (node (ref "IC3") (pin "4") (pinfunction "OUT_4") (pintype "input"))
      (node (ref "JP2") (pin "4") (pinfunction "4_4") (pintype "passive"))
      (node (ref "R42") (pin "2") (pinfunction "2_2") (pintype "passive"))
      (node (ref "U1") (pin "10") (pinfunction "OE_10") (pintype "input"))
      (node (ref "U1") (pin "2") (pinfunction "VCCA_2") (pintype "power_in"))
    )
    (net (code "2") (name "+5V") (class "Default")
      (node (ref "C1") (pin "1") (pinfunction "1_1") (pintype "passive"))
      (node (ref "C18") (pin "+") (pinfunction "+_+") (pintype "passive"))
      (node (ref "C26") (pin "1") (pinfunction "1_1") (pintype "passive"))
      (node (ref "C28") (pin "1") (pinfunction "1_1") (pintype "passive"))
      (node (ref "C34") (pin "1") (pinfunction "1_1") (pintype "passive"))
      (node (ref "C44") (pin "1") (pinfunction "1_1") (pintype "passive"))
      (node (ref "C45") (pin "1") (pinfunction "1_1") (pintype "passive"))
      (node (ref "C8") (pin "2") (pinfunction "2_2") (pintype "passive"))
      (node (ref "D2") (pin "K") (pinfunction "C_K") (pintype "passive"))
      (node (ref "IC2") (pin "16") (pinfunction "VDD_16") (pintype "power_in"))
      (node (ref "IC3") (pin "3") (pinfunction "IN_3") (pintype "input"))
      (node (ref "IC4") (pin "8") (pinfunction "V+_8") (pintype "power_in"))
      (node (ref "L5") (pin "1") (pinfunction "1_1") (pintype "passive"))
      (node (ref "OK2") (pin "8") (pinfunction "COL_8") (pintype "passive"))
      (node (ref "R17") (pin "2") (pinfunction "2_2") (pintype "passive"))
      (node (ref "R26") (pin "2") (pinfunction "2_2") (pintype "passive"))
      (node (ref "R43") (pin "2") (pinfunction "2_2") (pintype "passive"))
      (node (ref "R58") (pin "2") (pinfunction "2_2") (pintype "passive"))
      (node (ref "R70") (pin "1") (pinfunction "1_1") (pintype "passive"))
      (node (ref "S1") (pin "1") (pinfunction "S_1") (pintype "passive"))
      (node (ref "S1") (pin "2") (pinfunction "S1_2") (pintype "passive"))
      (node (ref "SV1") (pin "2") (pinfunction "2_2") (pintype "passive"))
      (node (ref "U$1") (pin "3") (pinfunction "VDD_3") (pintype "power_in"))
      (node (ref "U$2") (pin "4") (pinfunction "VCC_4") (pintype "bidirectional"))
      (node (ref "U1") (pin "19") (pinfunction "VCCB_19") (pintype "power_in"))
      (node (ref "U2") (pin "8") (pinfunction "VCC_8") (pintype "power_in"))
      (node (ref "U3") (pin "4") (pinfunction "FB_4") (pintype "input"))
    )
    (net (code "3") (name "+5V{slash}1") (class "Default")
      (node (ref "C40") (pin "+") (pinfunction "+_+") (pintype "passive"))
      (node (ref "JP3") (pin "2") (pinfunction "2_2") (pintype "passive"))
      (node (ref "JP4") (pin "2") (pinfunction "2_2") (pintype "passive"))
      (node (ref "L1") (pin "1") (pinfunction "1_1") (pintype "passive"))
      (node (ref "R45") (pin "2") (pinfunction "2_2") (pintype "passive"))
      (node (ref "U$8") (pin "4") (pinfunction "FB_4") (pintype "bidirectional"))
    )
    (net (code "4") (name "+5V{slash}3") (class "Default")
      (node (ref "C37") (pin "+") (pinfunction "+_+") (pintype "passive"))
      (node (ref "C39") (pin "1") (pinfunction "1_1") (pintype "passive"))
      (node (ref "C7") (pin "2") (pinfunction "2_2") (pintype "passive"))
      (node (ref "D14") (pin "C") (pinfunction "C_C") (pintype "passive"))
      (node (ref "OK1") (pin "6") (pinfunction "COL_6") (pintype "passive"))
      (node (ref "R30") (pin "1") (pinfunction "1_1") (pintype "passive"))
      (node (ref "R5") (pin "2") (pinfunction "2_2") (pintype "passive"))
      (node (ref "U$2") (pin "19") (pinfunction "AVCC_19") (pintype "bidirectional"))
    )
    (net (code "5") (name "+5V{slash}4") (class "Default")
      (node (ref "C16") (pin "1") (pinfunction "1_1") (pintype "passive"))
      (node (ref "C38") (pin "+") (pinfunction "+_+") (pintype "passive"))
      (node (ref "D12") (pin "C") (pinfunction "C_C") (pintype "passive"))
      (node (ref "OK1") (pin "8") (pinfunction "COL_8") (pintype "passive"))
      (node (ref "R29") (pin "1") (pinfunction "1_1") (pintype "passive"))
      (node (ref "R7") (pin "2") (pinfunction "2_2") (pintype "passive"))
    )
    (net (code "6") (name "+12V") (class "Default")
      (node (ref "C11") (pin "1") (pinfunction "1_1") (pintype "passive"))
      (node (ref "C21") (pin "+") (pinfunction "+_+") (pintype "passive"))
      (node (ref "L6") (pin "1") (pinfunction "1_1") (pintype "passive"))
      (node (ref "R44") (pin "2") (pinfunction "2_2") (pintype "passive"))
      (node (ref "U$3") (pin "12") (pinfunction "VCC_12") (pintype "bidirectional"))
      (node (ref "U4") (pin "4") (pinfunction "FB_4") (pintype "input"))
    )
    (net (code "7") (name "+24V") (class "Default")
      (node (ref "C17") (pin "+") (pinfunction "+_+") (pintype "passive"))
      (node (ref "C20") (pin "+") (pinfunction "+_+") (pintype "passive"))
      (node (ref "C3") (pin "+") (pinfunction "+_+") (pintype "passive"))
      (node (ref "C42") (pin "+") (pinfunction "+_+") (pintype "passive"))
      (node (ref "D1") (pin "K") (pinfunction "C_K") (pintype "passive"))
      (node (ref "F1") (pin "1") (pinfunction "1_1") (pintype "passive"))
      (node (ref "R30") (pin "2") (pinfunction "2_2") (pintype "passive"))
      (node (ref "R31") (pin "1") (pinfunction "1_1") (pintype "passive"))
      (node (ref "U$4") (pin "1") (pinfunction "U_IN_1") (pintype "bidirectional"))
      (node (ref "U$8") (pin "1") (pinfunction "VIN_1") (pintype "bidirectional"))
      (node (ref "U3") (pin "7") (pinfunction "VIN_7") (pintype "power_in"))
      (node (ref "U4") (pin "7") (pinfunction "VIN_7") (pintype "power_in"))
    )
    (net (code "8") (name "24V_PRI") (class "Default")
      (node (ref "C10") (pin "+") (pinfunction "+_+") (pintype "passive"))
      (node (ref "C35") (pin "1") (pinfunction "1_1") (pintype "passive"))
      (node (ref "C50") (pin "1") (pinfunction "1_1") (pintype "passive"))
      (node (ref "C9") (pin "+") (pinfunction "+_+") (pintype "passive"))
      (node (ref "Q3") (pin "D") (pinfunction "D_D") (pintype "passive"))
      (node (ref "Q5") (pin "4") (pinfunction "D_4") (pintype "passive"))
      (node (ref "R23") (pin "2") (pinfunction "2_2") (pintype "passive"))
      (node (ref "R27") (pin "2") (pinfunction "2_2") (pintype "passive"))
    )
    (net (code "9") (name "ACTIVATE_BOOSTER") (class "Default")
      (node (ref "R24") (pin "1") (pinfunction "1_1") (pintype "passive"))
      (node (ref "R25") (pin "1") (pinfunction "1_1") (pintype "passive"))
      (node (ref "U$2") (pin "26") (pinfunction "PB5_26") (pintype "bidirectional"))
    )
    (net (code "10") (name "ACTIVATE_SERVO") (class "Default")
      (node (ref "R47") (pin "1") (pinfunction "1_1") (pintype "passive"))
      (node (ref "U$2") (pin "15") (pinfunction "PD7_15") (pintype "bidirectional"))
    )
    (net (code "11") (name "ADC9{slash}FREI") (class "Default")
      (node (ref "U$2") (pin "18") (pinfunction "PC5_18") (pintype "bidirectional"))
    )
    (net (code "12") (name "ADC_24V_LOGIK{slash}SCK_A") (class "Default")
      (node (ref "R31") (pin "2") (pinfunction "2_2") (pintype "passive"))
      (node (ref "R50") (pin "1") (pinfunction "1_1") (pintype "passive"))
      (node (ref "SV1") (pin "7") (pinfunction "7_7") (pintype "passive"))
      (node (ref "U$2") (pin "12") (pinfunction "(RXD)PD4_12") (pintype "bidirectional"))
    )
    (net (code "13") (name "ADC_24V_PRI") (class "Default")
      (node (ref "R27") (pin "1") (pinfunction "1_1") (pintype "passive"))
      (node (ref "R28") (pin "2") (pinfunction "2_2") (pintype "passive"))
      (node (ref "U$2") (pin "13") (pinfunction "PD5_13") (pintype "bidirectional"))
    )
    (net (code "14") (name "ADC_CAP") (class "Default")
      (node (ref "C23") (pin "1") (pinfunction "1_1") (pintype "passive"))
      (node (ref "C47") (pin "1") (pinfunction "1_1") (pintype "passive"))
      (node (ref "IC4") (pin "3") (pinfunction "+IN_3") (pintype "input"))
      (node (ref "OK1") (pin "5") (pinfunction "EMIT_5") (pintype "passive"))
      (node (ref "R8") (pin "2") (pinfunction "2_2") (pintype "passive"))
      (node (ref "U$2") (pin "14") (pinfunction "PD6_14") (pintype "bidirectional"))
    )
    (net (code "15") (name "BOOSTER_24V") (class "Default")
      (node (ref "Q5") (pin "3") (pinfunction "S_3") (pintype "passive"))
      (node (ref "R200") (pin "2") (pinfunction "2_2") (pintype "passive"))
      (node (ref "R23") (pin "1") (pinfunction "1_1") (pintype "passive"))
      (node (ref "R46") (pin "2") (pinfunction "2_2") (pintype "passive"))
      (node (ref "X2") (pin "2") (pinfunction "KL_2") (pintype "passive"))
    )
    (net (code "16") (name "CAN_H") (class "Default")
      (node (ref "RJ_1") (pin "P$3") (pinfunction "P$3_P$3") (pintype "bidirectional"))
      (node (ref "RJ_2") (pin "P$3") (pinfunction "P$3_P$3") (pintype "bidirectional"))
      (node (ref "SJ1") (pin "2") (pinfunction "2_2") (pintype "passive"))
      (node (ref "U$1") (pin "7") (pinfunction "CANH_7") (pintype "bidirectional"))
    )
    (net (code "17") (name "CAN_L") (class "Default")
      (node (ref "R32") (pin "2") (pinfunction "2_2") (pintype "passive"))
      (node (ref "RJ_1") (pin "P$2") (pinfunction "P$2_P$2") (pintype "bidirectional"))
      (node (ref "RJ_2") (pin "P$2") (pinfunction "P$2_P$2") (pintype "bidirectional"))
      (node (ref "U$1") (pin "6") (pinfunction "CANL_6") (pintype "bidirectional"))
    )
    (net (code "18") (name "CAN_RX") (class "Default")
      (node (ref "U$1") (pin "4") (pinfunction "RXD_4") (pintype "output"))
      (node (ref "U$2") (pin "7") (pinfunction "(RXCAN)PC3_7") (pintype "bidirectional"))
    )
    (net (code "19") (name "CAN_TX") (class "Default")
      (node (ref "U$1") (pin "1") (pinfunction "TXD_1") (pintype "input"))
      (node (ref "U$2") (pin "6") (pinfunction "(TXCAN)PC2_6") (pintype "bidirectional"))
    )
    (net (code "20") (name "CAP_+12V") (class "Default")
      (node (ref "C29") (pin "+") (pinfunction "+_+") (pintype "passive"))
      (node (ref "C30") (pin "+") (pinfunction "+_+") (pintype "passive"))
      (node (ref "C31") (pin "+") (pinfunction "+_+") (pintype "passive"))
      (node (ref "C43") (pin "1") (pinfunction "1_1") (pintype "passive"))
      (node (ref "IC1") (pin "8") (pinfunction "V+_8") (pintype "power_in"))
      (node (ref "R29") (pin "2") (pinfunction "2_2") (pintype "passive"))
      (node (ref "R39") (pin "2") (pinfunction "2_2") (pintype "passive"))
      (node (ref "R40") (pin "2") (pinfunction "2_2") (pintype "passive"))
      (node (ref "R41") (pin "2") (pinfunction "2_2") (pintype "passive"))
      (node (ref "R49") (pin "2") (pinfunction "2_2") (pintype "passive"))
      (node (ref "T6") (pin "E") (pinfunction "E_E") (pintype "passive"))
      (node (ref "U$4") (pin "6") (pinfunction "+U_OUT_6") (pintype "bidirectional"))
      (node (ref "U$5") (pin "8") (pinfunction "VDD_8") (pintype "bidirectional"))
      (node (ref "U$6") (pin "8") (pinfunction "VDD_8") (pintype "bidirectional"))
    )
    (net (code "21") (name "CAP_0V") (class "Default")
      (node (ref "C14") (pin "2") (pinfunction "2_2") (pintype "passive"))
      (node (ref "C15") (pin "2") (pinfunction "2_2") (pintype "passive"))
      (node (ref "C16") (pin "2") (pinfunction "2_2") (pintype "passive"))
      (node (ref "C25") (pin "-") (pinfunction "-_-") (pintype "passive"))
      (node (ref "C29") (pin "-") (pinfunction "-_-") (pintype "passive"))
      (node (ref "C30") (pin "-") (pinfunction "-_-") (pintype "passive"))
      (node (ref "C31") (pin "-") (pinfunction "-_-") (pintype "passive"))
      (node (ref "C32") (pin "2") (pinfunction "2_2") (pintype "passive"))
      (node (ref "C38") (pin "-") (pinfunction "-_-") (pintype "passive"))
      (node (ref "C43") (pin "2") (pinfunction "2_2") (pintype "passive"))
      (node (ref "C46") (pin "2") (pinfunction "2_2") (pintype "passive"))
      (node (ref "C51") (pin "2") (pinfunction "2_2") (pintype "passive"))
      (node (ref "CAP_0V") (pin "P$1") (pinfunction "P_P$1") (pintype "passive"))
      (node (ref "D10") (pin "A") (pinfunction "A_A") (pintype "passive"))
      (node (ref "D11") (pin "A") (pinfunction "A_A") (pintype "passive"))
      (node (ref "D12") (pin "A") (pinfunction "A_A") (pintype "passive"))
      (node (ref "H1") (pin "B3,0") (pinfunction "MOUNT_B3,0") (pintype "passive"))
      (node (ref "IC1") (pin "4") (pinfunction "V-_4") (pintype "power_in"))
      (node (ref "LED9") (pin "C") (pinfunction "C_C") (pintype "passive"))
      (node (ref "OK1") (pin "4") (pinfunction "C_4") (pintype "passive"))
      (node (ref "OK2") (pin "2") (pinfunction "C_2") (pintype "passive"))
      (node (ref "Q2") (pin "S") (pinfunction "S_S") (pintype "passive"))
      (node (ref "Q6") (pin "S") (pinfunction "S_S") (pintype "passive"))
      (node (ref "R11") (pin "1") (pinfunction "1_1") (pintype "passive"))
      (node (ref "R12") (pin "1") (pinfunction "1_1") (pintype "passive"))
      (node (ref "R20") (pin "1") (pinfunction "1_1") (pintype "passive"))
      (node (ref "R36") (pin "1") (pinfunction "1_1") (pintype "passive"))
      (node (ref "R37") (pin "1") (pinfunction "1_1") (pintype "passive"))
      (node (ref "R38") (pin "1") (pinfunction "1_1") (pintype "passive"))
      (node (ref "R4") (pin "1") (pinfunction "1_1") (pintype "passive"))
      (node (ref "R6") (pin "1") (pinfunction "1_1") (pintype "passive"))
      (node (ref "U$4") (pin "4") (pinfunction "-U_OUT_4") (pintype "bidirectional"))
      (node (ref "U$5") (pin "5") (pinfunction "GND_5") (pintype "bidirectional"))
      (node (ref "U$6") (pin "5") (pinfunction "GND_5") (pintype "bidirectional"))
      (node (ref "VR1") (pin "3") (pinfunction "A_3") (pintype "passive"))
      (node (ref "VR2") (pin "3") (pinfunction "A_3") (pintype "passive"))
      (node (ref "VR3") (pin "3") (pinfunction "A_3") (pintype "passive"))
    )
    (net (code "22") (name "CAP_330V") (class "Default")
      (node (ref "C25") (pin "+") (pinfunction "+_+") (pintype "passive"))
      (node (ref "CAP_330V") (pin "P$1") (pinfunction "P_P$1") (pintype "passive"))
      (node (ref "COIL_OUT") (pin "P$1") (pinfunction "P_P$1") (pintype "passive"))
      (node (ref "D8") (pin "K") (pinfunction "C_K") (pintype "passive"))
      (node (ref "D9") (pin "K") (pinfunction "C_K") (pintype "passive"))
      (node (ref "R101") (pin "2") (pinfunction "2_2") (pintype "passive"))
      (node (ref "R2") (pin "1") (pinfunction "1_1") (pintype "passive"))
      (node (ref "R33") (pin "2") (pinfunction "2_2") (pintype "passive"))
      (node (ref "R34") (pin "2") (pinfunction "2_2") (pintype "passive"))
      (node (ref "R35") (pin "2") (pinfunction "2_2") (pintype "passive"))
      (node (ref "U$7") (pin "C") (pinfunction "C_C") (pintype "passive"))
    )
    (net (code "23") (name "CLKOUT_ETH") (class "Default")
      (node (ref "U1") (pin "12") (pinfunction "B8_12") (pintype "bidirectional"))
    )
    (net (code "24") (name "CLKOUT_ETH_3V") (class "Default")
      (node (ref "JP2") (pin "1") (pinfunction "1_1") (pintype "passive"))
      (node (ref "U1") (pin "9") (pinfunction "A8_9") (pintype "bidirectional"))
    )
    (net (code "25") (name "CS_ETH") (class "Default")
      (node (ref "U$2") (pin "29") (pinfunction "PD0_29") (pintype "bidirectional"))
      (node (ref "U1") (pin "13") (pinfunction "B7_13") (pintype "bidirectional"))
    )
    (net (code "26") (name "CS_ETH_3V") (class "Default")
      (node (ref "JP2") (pin "2") (pinfunction "2_2") (pintype "passive"))
      (node (ref "U1") (pin "8") (pinfunction "A7_8") (pintype "bidirectional"))
    )
    (net (code "27") (name "D2A") (class "Default")
      (node (ref "R52") (pin "1") (pinfunction "1_1") (pintype "passive"))
      (node (ref "U$2") (pin "25") (pinfunction "PC7_25") (pintype "bidirectional"))
    )
    (net (code "28") (name "FREI") (class "Default")
      (node (ref "U$2") (pin "16") (pinfunction "PB2_16") (pintype "bidirectional"))
    )
    (net (code "29") (name "FREI2") (class "Default")
      (node (ref "U$2") (pin "27") (pinfunction "PB6_27") (pintype "bidirectional"))
    )
    (net (code "30") (name "GND") (class "Default")
      (node (ref "C1") (pin "2") (pinfunction "2_2") (pintype "passive"))
      (node (ref "C11") (pin "2") (pinfunction "2_2") (pintype "passive"))
      (node (ref "C12") (pin "2") (pinfunction "2_2") (pintype "passive"))
      (node (ref "C17") (pin "-") (pinfunction "-_-") (pintype "passive"))
      (node (ref "C18") (pin "-") (pinfunction "-_-") (pintype "passive"))
      (node (ref "C2") (pin "2") (pinfunction "2_2") (pintype "passive"))
      (node (ref "C20") (pin "-") (pinfunction "-_-") (pintype "passive"))
      (node (ref "C21") (pin "-") (pinfunction "-_-") (pintype "passive"))
      (node (ref "C23") (pin "2") (pinfunction "2_2") (pintype "passive"))
      (node (ref "C24") (pin "2") (pinfunction "2_2") (pintype "passive"))
      (node (ref "C26") (pin "2") (pinfunction "2_2") (pintype "passive"))
      (node (ref "C27") (pin "2") (pinfunction "2_2") (pintype "passive"))
      (node (ref "C28") (pin "2") (pinfunction "2_2") (pintype "passive"))
      (node (ref "C3") (pin "-") (pinfunction "-_-") (pintype "passive"))
      (node (ref "C33") (pin "2") (pinfunction "2_2") (pintype "passive"))
      (node (ref "C34") (pin "2") (pinfunction "2_2") (pintype "passive"))
      (node (ref "C36") (pin "2") (pinfunction "2_2") (pintype "passive"))
      (node (ref "C37") (pin "-") (pinfunction "-_-") (pintype "passive"))
      (node (ref "C39") (pin "2") (pinfunction "2_2") (pintype "passive"))
      (node (ref "C4") (pin "1") (pinfunction "1_1") (pintype "passive"))
      (node (ref "C40") (pin "-") (pinfunction "-_-") (pintype "passive"))
      (node (ref "C41") (pin "2") (pinfunction "2_2") (pintype "passive"))
      (node (ref "C42") (pin "-") (pinfunction "-_-") (pintype "passive"))
      (node (ref "C44") (pin "2") (pinfunction "2_2") (pintype "passive"))
      (node (ref "C45") (pin "2") (pinfunction "2_2") (pintype "passive"))
      (node (ref "C47") (pin "2") (pinfunction "2_2") (pintype "passive"))
      (node (ref "C48") (pin "2") (pinfunction "2_2") (pintype "passive"))
      (node (ref "C49") (pin "2") (pinfunction "2_2") (pintype "passive"))
      (node (ref "C5") (pin "1") (pinfunction "1_1") (pintype "passive"))
      (node (ref "C6") (pin "1") (pinfunction "1_1") (pintype "passive"))
      (node (ref "C7") (pin "1") (pinfunction "1_1") (pintype "passive"))
      (node (ref "C8") (pin "1") (pinfunction "1_1") (pintype "passive"))
      (node (ref "CF") (pin "2") (pinfunction "2_2") (pintype "passive"))
      (node (ref "CSS") (pin "2") (pinfunction "2_2") (pintype "passive"))
      (node (ref "C_DELAY") (pin "2") (pinfunction "2_2") (pintype "passive"))
      (node (ref "C_ISEN_B") (pin "2") (pinfunction "2_2") (pintype "passive"))
      (node (ref "D1") (pin "A") (pinfunction "A_A") (pintype "passive"))
      (node (ref "D14") (pin "A") (pinfunction "A_A") (pintype "passive"))
      (node (ref "D15") (pin "A") (pinfunction "A_A") (pintype "passive"))
      (node (ref "D4") (pin "A") (pinfunction "A_A") (pintype "passive"))
      (node (ref "D6") (pin "A") (pinfunction "A_A") (pintype "passive"))
      (node (ref "D7") (pin "A") (pinfunction "A_A") (pintype "passive"))
      (node (ref "H2") (pin "B3,0") (pinfunction "MOUNT_B3,0") (pintype "passive"))
      (node (ref "H3") (pin "B3,0") (pinfunction "MOUNT_B3,0") (pintype "passive"))
      (node (ref "H4") (pin "B3,0") (pinfunction "MOUNT_B3,0") (pintype "passive"))
      (node (ref "IC2") (pin "3") (pinfunction "R0_3") (pintype "input"))
      (node (ref "IC2") (pin "4") (pinfunction "S0_4") (pintype "input"))
      (node (ref "IC2") (pin "6") (pinfunction "S1_6") (pintype "input"))
      (node (ref "IC2") (pin "7") (pinfunction "R1_7") (pintype "input"))
      (node (ref "IC2") (pin "8") (pinfunction "VSS_8") (pintype "power_in"))
      (node (ref "IC3") (pin "1") (pinfunction "GND_1") (pintype "input"))
      (node (ref "IC4") (pin "4") (pinfunction "V-_4") (pintype "power_in"))
      (node (ref "IC4") (pin "5") (pinfunction "+IN_5") (pintype "input"))
      (node (ref "IC4") (pin "6") (pinfunction "-IN_6") (pintype "input"))
      (node (ref "JP2") (pin "5") (pinfunction "5_5") (pintype "passive"))
      (node (ref "JP4") (pin "3") (pinfunction "3_3") (pintype "passive"))
      (node (ref "LED10") (pin "C") (pinfunction "C_C") (pintype "passive"))
      (node (ref "LED4") (pin "C") (pinfunction "C_C") (pintype "passive"))
      (node (ref "LED5") (pin "C") (pinfunction "C_C") (pintype "passive"))
      (node (ref "LED6") (pin "C") (pinfunction "C_C") (pintype "passive"))
      (node (ref "LED7") (pin "C") (pinfunction "C_C") (pintype "passive"))
      (node (ref "R1") (pin "1") (pinfunction "1_1") (pintype "passive"))
      (node (ref "R10") (pin "1") (pinfunction "1_1") (pintype "passive"))
      (node (ref "R16") (pin "1") (pinfunction "1_1") (pintype "passive"))
      (node (ref "R21") (pin "1") (pinfunction "1_1") (pintype "passive"))
      (node (ref "R22") (pin "1") (pinfunction "1_1") (pintype "passive"))
      (node (ref "R28") (pin "1") (pinfunction "1_1") (pintype "passive"))
      (node (ref "R50") (pin "2") (pinfunction "2_2") (pintype "passive"))
      (node (ref "R51") (pin "1") (pinfunction "1_1") (pintype "passive"))
      (node (ref "R8") (pin "1") (pinfunction "1_1") (pintype "passive"))
      (node (ref "RF_MIN") (pin "1") (pinfunction "1_1") (pintype "passive"))
      (node (ref "RJ_1") (pin "P$4") (pinfunction "P$4_P$4") (pintype "bidirectional"))
      (node (ref "RJ_2") (pin "P$4") (pinfunction "P$4_P$4") (pintype "bidirectional"))
      (node (ref "R_DELAY") (pin "1") (pinfunction "1_1") (pintype "passive"))
      (node (ref "R_ISEN_B") (pin "1") (pinfunction "1_1") (pintype "passive"))
      (node (ref "SV1") (pin "10") (pinfunction "10_10") (pintype "passive"))
      (node (ref "SV1") (pin "4") (pinfunction "4_4") (pintype "passive"))
      (node (ref "SV1") (pin "6") (pinfunction "6_6") (pintype "passive"))
      (node (ref "SV1") (pin "8") (pinfunction "8_8") (pintype "passive"))
      (node (ref "T1") (pin "2") (pinfunction "E_2") (pintype "passive"))
      (node (ref "T2") (pin "2") (pinfunction "E_2") (pintype "passive"))
      (node (ref "T4") (pin "2") (pinfunction "E_2") (pintype "passive"))
      (node (ref "T5") (pin "2") (pinfunction "S_2") (pintype "passive"))
      (node (ref "T8") (pin "2") (pinfunction "E_2") (pintype "passive"))
      (node (ref "U$1") (pin "2") (pinfunction "VSS_2") (pintype "passive"))
      (node (ref "U$2") (pin "20") (pinfunction "AGND_20") (pintype "power_in"))
      (node (ref "U$2") (pin "5") (pinfunction "GND_5") (pintype "power_in"))
      (node (ref "U$3") (pin "10") (pinfunction "GND_10") (pintype "bidirectional"))
      (node (ref "U$3") (pin "8") (pinfunction "DIS_8") (pintype "bidirectional"))
      (node (ref "U$4") (pin "2") (pinfunction "GND_2") (pintype "bidirectional"))
      (node (ref "U$5") (pin "1") (pinfunction "NC_1") (pintype "bidirectional"))
      (node (ref "U$5") (pin "3") (pinfunction "CATHODE_3") (pintype "bidirectional"))
      (node (ref "U$5") (pin "4") (pinfunction "NC_4") (pintype "bidirectional"))
      (node (ref "U$6") (pin "1") (pinfunction "NC_1") (pintype "bidirectional"))
      (node (ref "U$6") (pin "4") (pinfunction "NC_4") (pintype "bidirectional"))
      (node (ref "U$8") (pin "3") (pinfunction "GND_3") (pintype "bidirectional"))
      (node (ref "U$8") (pin "5") (pinfunction "~{ON}/OFF_5") (pintype "bidirectional"))
      (node (ref "U1") (pin "11") (pinfunction "GND_11") (pintype "passive"))
      (node (ref "U2") (pin "4") (pinfunction "GND_4") (pintype "passive"))
      (node (ref "U3") (pin "6") (pinfunction "GND_6") (pintype "passive"))
      (node (ref "U4") (pin "6") (pinfunction "GND_6") (pintype "passive"))
      (node (ref "X1") (pin "2") (pinfunction "KL_2") (pintype "passive"))
    )
    (net (code "31") (name "GND1") (class "Default")
      (node (ref "C10") (pin "-") (pinfunction "-_-") (pintype "passive"))
      (node (ref "C13") (pin "2") (pinfunction "2_2") (pintype "passive"))
      (node (ref "C35") (pin "2") (pinfunction "2_2") (pintype "passive"))
      (node (ref "C50") (pin "2") (pinfunction "2_2") (pintype "passive"))
      (node (ref "C9") (pin "-") (pinfunction "-_-") (pintype "passive"))
      (node (ref "LED8") (pin "C") (pinfunction "C_C") (pintype "passive"))
      (node (ref "Q4") (pin "S") (pinfunction "S_S") (pintype "passive"))
      (node (ref "R54") (pin "2") (pinfunction "2_2") (pintype "passive"))
      (node (ref "T3") (pin "2") (pinfunction "E_2") (pintype "passive"))
      (node (ref "X2") (pin "1") (pinfunction "KL_1") (pintype "passive"))
    )
    (net (code "32") (name "INT_ETH") (class "Default")
      (node (ref "U$2") (pin "30") (pinfunction "PC0_30") (pintype "bidirectional"))
      (node (ref "U1") (pin "20") (pinfunction "B1_20") (pintype "bidirectional"))
    )
    (net (code "33") (name "INT_ETH_3V") (class "Default")
      (node (ref "JP1") (pin "5") (pinfunction "5_5") (pintype "passive"))
      (node (ref "U1") (pin "1") (pinfunction "A1_1") (pintype "bidirectional"))
    )
    (net (code "34") (name "KICK") (class "Default")
      (node (ref "R19") (pin "1") (pinfunction "1_1") (pintype "passive"))
      (node (ref "U$2") (pin "23") (pinfunction "PB3_23") (pintype "bidirectional"))
    )
    (net (code "35") (name "LINE") (class "Default")
      (node (ref "C48") (pin "1") (pinfunction "1_1") (pintype "passive"))
      (node (ref "R70") (pin "2") (pinfunction "2_2") (pintype "passive"))
      (node (ref "T1") (pin "3") (pinfunction "C_3") (pintype "passive"))
      (node (ref "T2") (pin "3") (pinfunction "C_3") (pintype "passive"))
      (node (ref "U$3") (pin "7") (pinfunction "LINE_7") (pintype "bidirectional"))
      (node (ref "U$6") (pin "3") (pinfunction "CATHODE_3") (pintype "bidirectional"))
    )
    (net (code "36") (name "MISO") (class "Default")
      (node (ref "U$2") (pin "8") (pinfunction "PB0_8") (pintype "bidirectional"))
      (node (ref "U1") (pin "17") (pinfunction "B3_17") (pintype "bidirectional"))
    )
    (net (code "37") (name "MISO_3V") (class "Default")
      (node (ref "JP1") (pin "3") (pinfunction "3_3") (pintype "passive"))
      (node (ref "U1") (pin "4") (pinfunction "A3_4") (pintype "bidirectional"))
    )
    (net (code "38") (name "MOSI") (class "Default")
      (node (ref "U$2") (pin "9") (pinfunction "PB1_9") (pintype "bidirectional"))
      (node (ref "U1") (pin "16") (pinfunction "B4_16") (pintype "bidirectional"))
    )
    (net (code "39") (name "MOSI_3V") (class "Default")
      (node (ref "JP1") (pin "2") (pinfunction "2_2") (pintype "passive"))
      (node (ref "U1") (pin "5") (pinfunction "A4_5") (pintype "bidirectional"))
    )
    (net (code "40") (name "NOTAUS") (class "Default")
      (node (ref "R14") (pin "1") (pinfunction "1_1") (pintype "passive"))
      (node (ref "R55") (pin "2") (pinfunction "2_2") (pintype "passive"))
      (node (ref "R61") (pin "1") (pinfunction "1_1") (pintype "passive"))
      (node (ref "U2") (pin "7") (pinfunction "1Y_7") (pintype "output"))
    )
    (net (code "41") (name "Net-(COIL_IN-P)") (class "Default")
      (node (ref "COIL_IN") (pin "P$1") (pinfunction "P_P$1") (pintype "passive"))
      (node (ref "Q2") (pin "D") (pinfunction "D_D") (pintype "passive"))
      (node (ref "R20") (pin "2") (pinfunction "2_2") (pintype "passive"))
      (node (ref "U$7") (pin "A") (pinfunction "A_A") (pintype "passive"))
    )
    (net (code "42") (name "Net-(C_ISEN_A-Pad1)") (class "Default")
      (node (ref "C_ISEN_A") (pin "1") (pinfunction "1_1") (pintype "passive"))
      (node (ref "R_ISEN_A") (pin "2") (pinfunction "2_2") (pintype "passive"))
    )
    (net (code "43") (name "Net-(D3-PadA)") (class "Default")
      (node (ref "D3") (pin "A") (pinfunction "A_A") (pintype "passive"))
      (node (ref "D4") (pin "C") (pinfunction "C_C") (pintype "passive"))
      (node (ref "R_ISEN_A") (pin "1") (pinfunction "1_1") (pintype "passive"))
    )
    (net (code "44") (name "Net-(D5-C)") (class "Default")
      (node (ref "D5") (pin "K") (pinfunction "C_K") (pintype "passive"))
      (node (ref "R18") (pin "1") (pinfunction "1_1") (pintype "passive"))
      (node (ref "U$6") (pin "6") (pinfunction "VO_6") (pintype "bidirectional"))
      (node (ref "U$6") (pin "7") (pinfunction "VO_7") (pintype "bidirectional"))
    )
    (net (code "45") (name "Net-(D5-PadA)") (class "Default")
      (node (ref "D5") (pin "A") (pinfunction "A_A") (pintype "passive"))
      (node (ref "R13") (pin "1") (pinfunction "1_1") (pintype "passive"))
    )
    (net (code "46") (name "Net-(D6-C)") (class "Default")
      (node (ref "C19") (pin "2") (pinfunction "2_2") (pintype "passive"))
      (node (ref "D6") (pin "K") (pinfunction "C_K") (pintype "passive"))
      (node (ref "L5") (pin "2") (pinfunction "2_2") (pintype "passive"))
      (node (ref "U3") (pin "8") (pinfunction "VSW_8") (pintype "output"))
    )
    (net (code "47") (name "Net-(D7-C)") (class "Default")
      (node (ref "C22") (pin "2") (pinfunction "2_2") (pintype "passive"))
      (node (ref "D7") (pin "K") (pinfunction "C_K") (pintype "passive"))
      (node (ref "L6") (pin "2") (pinfunction "2_2") (pintype "passive"))
      (node (ref "U4") (pin "8") (pinfunction "VSW_8") (pintype "output"))
    )
    (net (code "48") (name "Net-(D10-C)") (class "Default")
      (node (ref "D10") (pin "K") (pinfunction "C_K") (pintype "passive"))
      (node (ref "D8") (pin "A") (pinfunction "A_A") (pintype "passive"))
      (node (ref "L7") (pin "2") (pinfunction "8_2") (pintype "passive"))
    )
    (net (code "49") (name "Net-(D11-C)") (class "Default")
      (node (ref "D11") (pin "K") (pinfunction "C_K") (pintype "passive"))
      (node (ref "D9") (pin "A") (pinfunction "A_A") (pintype "passive"))
      (node (ref "L7") (pin "4") (pinfunction "1_4") (pintype "passive"))
    )
    (net (code "50") (name "Net-(D15-C)") (class "Default")
      (node (ref "D15") (pin "K") (pinfunction "C_K") (pintype "passive"))
      (node (ref "L1") (pin "2") (pinfunction "2_2") (pintype "passive"))
      (node (ref "U$8") (pin "2") (pinfunction "VOUT_2") (pintype "bidirectional"))
    )
    (net (code "51") (name "Net-(IC1A-+IN)") (class "Default")
      (node (ref "C15") (pin "1") (pinfunction "1_1") (pintype "passive"))
      (node (ref "C32") (pin "1") (pinfunction "1_1") (pintype "passive"))
      (node (ref "IC1") (pin "3") (pinfunction "+IN_3") (pintype "input"))
      (node (ref "IC1") (pin "5") (pinfunction "+IN_5") (pintype "input"))
      (node (ref "R101") (pin "1") (pinfunction "1_1") (pintype "passive"))
      (node (ref "R6") (pin "2") (pinfunction "2_2") (pintype "passive"))
    )
    (net (code "52") (name "Net-(IC1A--IN)") (class "Default")
      (node (ref "C14") (pin "1") (pinfunction "1_1") (pintype "passive"))
      (node (ref "C51") (pin "1") (pinfunction "1_1") (pintype "passive"))
      (node (ref "IC1") (pin "2") (pinfunction "-IN_2") (pintype "input"))
      (node (ref "OK1") (pin "7") (pinfunction "EMIT_7") (pintype "passive"))
      (node (ref "R11") (pin "2") (pinfunction "2_2") (pintype "passive"))
    )
    (net (code "53") (name "Net-(IC1A-OUT)") (class "Default")
      (node (ref "IC1") (pin "1") (pinfunction "OUT_1") (pintype "output"))
      (node (ref "R105") (pin "1") (pinfunction "1_1") (pintype "passive"))
    )
    (net (code "54") (name "Net-(IC1B--IN)") (class "Default")
      (node (ref "C46") (pin "1") (pinfunction "1_1") (pintype "passive"))
      (node (ref "IC1") (pin "6") (pinfunction "-IN_6") (pintype "input"))
      (node (ref "R4") (pin "2") (pinfunction "2_2") (pintype "passive"))
      (node (ref "R7") (pin "1") (pinfunction "1_1") (pintype "passive"))
    )
    (net (code "55") (name "Net-(IC1B-OUT)") (class "Default")
      (node (ref "IC1") (pin "7") (pinfunction "OUT_7") (pintype "output"))
      (node (ref "R9") (pin "1") (pinfunction "1_1") (pintype "passive"))
    )
    (net (code "56") (name "Net-(IC2A-EN)") (class "Default")
      (node (ref "IC2") (pin "5") (pinfunction "EN_5") (pintype "input"))
      (node (ref "R58") (pin "1") (pinfunction "1_1") (pintype "passive"))
    )
    (net (code "57") (name "Net-(IC2A-Q2)") (class "Default")
      (node (ref "IC2") (pin "10") (pinfunction "Q2_10") (pintype "output"))
      (node (ref "U2") (pin "1") (pinfunction "1A_1") (pintype "input"))
    )
    (net (code "58") (name "Net-(IC2A-Q3)") (class "Default")
      (node (ref "IC2") (pin "1") (pinfunction "Q3_1") (pintype "output"))
      (node (ref "U2") (pin "5") (pinfunction "2A_5") (pintype "input"))
    )
    (net (code "59") (name "Net-(IC4A--IN)") (class "Default")
      (node (ref "C36") (pin "1") (pinfunction "1_1") (pintype "passive"))
      (node (ref "IC4") (pin "2") (pinfunction "-IN_2") (pintype "input"))
      (node (ref "R21") (pin "2") (pinfunction "2_2") (pintype "passive"))
      (node (ref "R5") (pin "1") (pinfunction "1_1") (pintype "passive"))
      (node (ref "R52") (pin "2") (pinfunction "2_2") (pintype "passive"))
    )
    (net (code "60") (name "Net-(IC4A-OUT)") (class "Default")
      (node (ref "IC4") (pin "1") (pinfunction "OUT_1") (pintype "output"))
      (node (ref "U2") (pin "6") (pinfunction "2B_6") (pintype "input"))
    )
    (net (code "61") (name "Net-(L7-4)") (class "Default")
      (node (ref "L3") (pin "1") (pinfunction "1_1") (pintype "passive"))
      (node (ref "L4") (pin "1") (pinfunction "1_1") (pintype "passive"))
      (node (ref "L7") (pin "9") (pinfunction "4_9") (pintype "passive"))
    )
    (net (code "62") (name "Net-(L7-5)") (class "Default")
      (node (ref "C13") (pin "1") (pinfunction "1_1") (pintype "passive"))
      (node (ref "C_ISEN_A") (pin "2") (pinfunction "2_2") (pintype "passive"))
      (node (ref "L3") (pin "2") (pinfunction "2_2") (pintype "passive"))
      (node (ref "L7") (pin "11") (pinfunction "5_11") (pintype "passive"))
    )
    (net (code "63") (name "Net-(LED1-PadA)") (class "Default")
      (node (ref "LED1") (pin "A") (pinfunction "A_A") (pintype "passive"))
      (node (ref "R39") (pin "1") (pinfunction "1_1") (pintype "passive"))
    )
    (net (code "64") (name "Net-(LED2-PadA)") (class "Default")
      (node (ref "LED2") (pin "A") (pinfunction "A_A") (pintype "passive"))
      (node (ref "R40") (pin "1") (pinfunction "1_1") (pintype "passive"))
    )
    (net (code "65") (name "Net-(LED3-PadA)") (class "Default")
      (node (ref "LED3") (pin "A") (pinfunction "A_A") (pintype "passive"))
      (node (ref "R41") (pin "1") (pinfunction "1_1") (pintype "passive"))
    )
    (net (code "66") (name "Net-(LED4-PadA)") (class "Default")
      (node (ref "LED4") (pin "A") (pinfunction "A_A") (pintype "passive"))
      (node (ref "R42") (pin "1") (pinfunction "1_1") (pintype "passive"))
    )
    (net (code "67") (name "Net-(LED5-PadA)") (class "Default")
      (node (ref "LED5") (pin "A") (pinfunction "A_A") (pintype "passive"))
      (node (ref "R43") (pin "1") (pinfunction "1_1") (pintype "passive"))
    )
    (net (code "68") (name "Net-(LED6-PadA)") (class "Default")
      (node (ref "LED6") (pin "A") (pinfunction "A_A") (pintype "passive"))
      (node (ref "R44") (pin "1") (pinfunction "1_1") (pintype "passive"))
    )
    (net (code "69") (name "Net-(LED7-PadA)") (class "Default")
      (node (ref "LED7") (pin "A") (pinfunction "A_A") (pintype "passive"))
      (node (ref "R45") (pin "1") (pinfunction "1_1") (pintype "passive"))
    )
    (net (code "70") (name "Net-(LED8-PadA)") (class "Default")
      (node (ref "LED8") (pin "A") (pinfunction "A_A") (pintype "passive"))
      (node (ref "R46") (pin "1") (pinfunction "1_1") (pintype "passive"))
    )
    (net (code "71") (name "Net-(LED9-PadA)") (class "Default")
      (node (ref "LED9") (pin "A") (pinfunction "A_A") (pintype "passive"))
      (node (ref "R49") (pin "1") (pinfunction "1_1") (pintype "passive"))
    )
    (net (code "72") (name "Net-(LED10-PadA)") (class "Default")
      (node (ref "LED10") (pin "A") (pinfunction "A_A") (pintype "passive"))
      (node (ref "R59") (pin "1") (pinfunction "1_1") (pintype "passive"))
    )
    (net (code "73") (name "Net-(OK1A-A)") (class "Default")
      (node (ref "OK1") (pin "1") (pinfunction "A_1") (pintype "passive"))
      (node (ref "R105") (pin "2") (pinfunction "2_2") (pintype "passive"))
    )
    (net (code "74") (name "Net-(OK1A-C)") (class "Default")
      (node (ref "OK1") (pin "2") (pinfunction "C_2") (pintype "passive"))
      (node (ref "OK1") (pin "3") (pinfunction "A_3") (pintype "passive"))
    )
    (net (code "75") (name "Net-(OK2A-A)") (class "Default")
      (node (ref "OK2") (pin "1") (pinfunction "A_1") (pintype "passive"))
      (node (ref "R9") (pin "2") (pinfunction "2_2") (pintype "passive"))
    )
    (net (code "76") (name "Net-(Q2-PadG)") (class "Default")
      (node (ref "Q2") (pin "G") (pinfunction "G_G") (pintype "passive"))
      (node (ref "R13") (pin "2") (pinfunction "2_2") (pintype "passive"))
      (node (ref "R18") (pin "2") (pinfunction "2_2") (pintype "passive"))
    )
    (net (code "77") (name "Net-(Q5-G)") (class "Default")
      (node (ref "D13") (pin "C") (pinfunction "C_C") (pintype "passive"))
      (node (ref "Q5") (pin "1") (pinfunction "G_1") (pintype "passive"))
      (node (ref "R200") (pin "1") (pinfunction "1_1") (pintype "passive"))
    )
    (net (code "78") (name "Net-(Q6-PadD)") (class "Default")
      (node (ref "Q6") (pin "D") (pinfunction "D_D") (pintype "passive"))
      (node (ref "R3") (pin "2") (pinfunction "2_2") (pintype "passive"))
    )
    (net (code "79") (name "Net-(Q6-PadG)") (class "Default")
      (node (ref "Q6") (pin "G") (pinfunction "G_G") (pintype "passive"))
      (node (ref "R12") (pin "2") (pinfunction "2_2") (pintype "passive"))
      (node (ref "T6") (pin "C") (pinfunction "C_C") (pintype "passive"))
    )
    (net (code "80") (name "Net-(R2-Pad2)") (class "Default")
      (node (ref "R2") (pin "2") (pinfunction "2_2") (pintype "passive"))
      (node (ref "R3") (pin "1") (pinfunction "1_1") (pintype "passive"))
    )
    (net (code "81") (name "Net-(R15-Pad1)") (class "Default")
      (node (ref "R15") (pin "1") (pinfunction "1_1") (pintype "passive"))
      (node (ref "U$5") (pin "6") (pinfunction "VO_6") (pintype "bidirectional"))
      (node (ref "U$5") (pin "7") (pinfunction "VO_7") (pintype "bidirectional"))
    )
    (net (code "82") (name "Net-(R15-Pad2)") (class "Default")
      (node (ref "R15") (pin "2") (pinfunction "2_2") (pintype "passive"))
      (node (ref "T6") (pin "B") (pinfunction "B_B") (pintype "passive"))
    )
    (net (code "83") (name "Net-(R32-Pad1)") (class "Default")
      (node (ref "R32") (pin "1") (pinfunction "1_1") (pintype "passive"))
      (node (ref "SJ1") (pin "1") (pinfunction "1_1") (pintype "passive"))
    )
    (net (code "84") (name "Net-(T1-B)") (class "Default")
      (node (ref "R61") (pin "2") (pinfunction "2_2") (pintype "passive"))
      (node (ref "T1") (pin "1") (pinfunction "B_1") (pintype "passive"))
    )
    (net (code "85") (name "Net-(T2-B)") (class "Default")
      (node (ref "R19") (pin "2") (pinfunction "2_2") (pintype "passive"))
      (node (ref "R51") (pin "2") (pinfunction "2_2") (pintype "passive"))
      (node (ref "T2") (pin "1") (pinfunction "B_1") (pintype "passive"))
    )
    (net (code "86") (name "Net-(T3-B)") (class "Default")
      (node (ref "R24") (pin "2") (pinfunction "2_2") (pintype "passive"))
      (node (ref "T3") (pin "1") (pinfunction "B_1") (pintype "passive"))
    )
    (net (code "87") (name "Net-(T3-C)") (class "Default")
      (node (ref "D13") (pin "A") (pinfunction "A_A") (pintype "passive"))
      (node (ref "T3") (pin "3") (pinfunction "C_3") (pintype "passive"))
    )
    (net (code "88") (name "Net-(T4-B)") (class "Default")
      (node (ref "R25") (pin "2") (pinfunction "2_2") (pintype "passive"))
      (node (ref "T4") (pin "1") (pinfunction "B_1") (pintype "passive"))
    )
    (net (code "89") (name "Net-(T4-C)") (class "Default")
      (node (ref "R26") (pin "1") (pinfunction "1_1") (pintype "passive"))
      (node (ref "T4") (pin "3") (pinfunction "C_3") (pintype "passive"))
      (node (ref "U2") (pin "2") (pinfunction "1B_2") (pintype "input"))
    )
    (net (code "90") (name "Net-(T5-D)") (class "Default")
      (node (ref "JP3") (pin "3") (pinfunction "3_3") (pintype "passive"))
      (node (ref "T5") (pin "1") (pinfunction "D_1") (pintype "passive"))
    )
    (net (code "91") (name "Net-(T5-G)") (class "Default")
      (node (ref "R16") (pin "2") (pinfunction "2_2") (pintype "passive"))
      (node (ref "R47") (pin "2") (pinfunction "2_2") (pintype "passive"))
      (node (ref "T5") (pin "3") (pinfunction "G_3") (pintype "passive"))
    )
    (net (code "92") (name "Net-(T8-B)") (class "Default")
      (node (ref "C49") (pin "1") (pinfunction "1_1") (pintype "passive"))
      (node (ref "R48") (pin "2") (pinfunction "2_2") (pintype "passive"))
      (node (ref "T8") (pin "1") (pinfunction "B_1") (pintype "passive"))
    )
    (net (code "93") (name "Net-(T8-C)") (class "Default")
      (node (ref "RF_MAX") (pin "1") (pinfunction "1_1") (pintype "passive"))
      (node (ref "T8") (pin "3") (pinfunction "C_3") (pintype "passive"))
    )
    (net (code "94") (name "Net-(U$1-RS)") (class "Default")
      (node (ref "R1") (pin "2") (pinfunction "2_2") (pintype "passive"))
      (node (ref "U$1") (pin "8") (pinfunction "RS_8") (pintype "input"))
    )
    (net (code "95") (name "Net-(U$2-AREF)") (class "Default")
      (node (ref "C6") (pin "2") (pinfunction "2_2") (pintype "passive"))
      (node (ref "U$2") (pin "21") (pinfunction "AREF_21") (pintype "bidirectional"))
    )
    (net (code "96") (name "Net-(U$2-PC4)") (class "Default")
      (node (ref "R57") (pin "1") (pinfunction "1_1") (pintype "passive"))
      (node (ref "U$2") (pin "17") (pinfunction "PC4_17") (pintype "bidirectional"))
    )
    (net (code "97") (name "Net-(U$2-PC6)") (class "Default")
      (node (ref "R55") (pin "1") (pinfunction "1_1") (pintype "passive"))
      (node (ref "U$2") (pin "22") (pinfunction "PC6_22") (pintype "bidirectional"))
    )
    (net (code "98") (name "Net-(U$2-PE1(XTAL1))") (class "Default")
      (node (ref "C5") (pin "2") (pinfunction "2_2") (pintype "passive"))
      (node (ref "Q1") (pin "1") (pinfunction "1_1") (pintype "passive"))
      (node (ref "U$2") (pin "10") (pinfunction "PE1(XTAL1)_10") (pintype "bidirectional"))
    )
    (net (code "99") (name "Net-(U$2-PE2(XTAL2))") (class "Default")
      (node (ref "C4") (pin "2") (pinfunction "2_2") (pintype "passive"))
      (node (ref "Q1") (pin "2") (pinfunction "2_2") (pintype "passive"))
      (node (ref "U$2") (pin "11") (pinfunction "PE2(XTAL2)_11") (pintype "bidirectional"))
    )
    (net (code "100") (name "Net-(U$3-CF)") (class "Default")
      (node (ref "CF") (pin "1") (pinfunction "1_1") (pintype "passive"))
      (node (ref "U$3") (pin "3") (pinfunction "CF_3") (pintype "bidirectional"))
    )
    (net (code "101") (name "Net-(U$3-CSS)") (class "Default")
      (node (ref "CSS") (pin "1") (pinfunction "1_1") (pintype "passive"))
      (node (ref "R_SS") (pin "1") (pinfunction "1_1") (pintype "passive"))
      (node (ref "U$3") (pin "1") (pinfunction "CSS_1") (pintype "bidirectional"))
    )
    (net (code "102") (name "Net-(U$3-DELAY)") (class "Default")
      (node (ref "C_DELAY") (pin "1") (pinfunction "1_1") (pintype "passive"))
      (node (ref "R_DELAY") (pin "2") (pinfunction "2_2") (pintype "passive"))
      (node (ref "U$3") (pin "2") (pinfunction "DELAY_2") (pintype "bidirectional"))
    )
    (net (code "103") (name "Net-(U$3-HVG)") (class "Default")
      (node (ref "Q3") (pin "G") (pinfunction "G_G") (pintype "passive"))
      (node (ref "R53") (pin "1") (pinfunction "1_1") (pintype "passive"))
      (node (ref "U$3") (pin "15") (pinfunction "HVG_15") (pintype "bidirectional"))
    )
    (net (code "104") (name "Net-(U$3-ISEN)") (class "Default")
      (node (ref "C_ISEN_B") (pin "1") (pinfunction "1_1") (pintype "passive"))
      (node (ref "D3") (pin "C") (pinfunction "C_C") (pintype "passive"))
      (node (ref "R_ISEN_B") (pin "2") (pinfunction "2_2") (pintype "passive"))
      (node (ref "U$3") (pin "6") (pinfunction "ISEN_6") (pintype "bidirectional"))
    )
    (net (code "105") (name "Net-(U$3-LVG)") (class "Default")
      (node (ref "Q4") (pin "G") (pinfunction "G_G") (pintype "passive"))
      (node (ref "R54") (pin "1") (pinfunction "1_1") (pintype "passive"))
      (node (ref "U$3") (pin "11") (pinfunction "LVG_11") (pintype "bidirectional"))
    )
    (net (code "106") (name "Net-(U$3-OUT)") (class "Default")
      (node (ref "C_BOOT") (pin "2") (pinfunction "2_2") (pintype "passive"))
      (node (ref "L4") (pin "2") (pinfunction "2_2") (pintype "passive"))
      (node (ref "Q3") (pin "S") (pinfunction "S_S") (pintype "passive"))
      (node (ref "Q4") (pin "D") (pinfunction "D_D") (pintype "passive"))
      (node (ref "R53") (pin "2") (pinfunction "2_2") (pintype "passive"))
      (node (ref "U$3") (pin "14") (pinfunction "OUT_14") (pintype "bidirectional"))
    )
    (net (code "107") (name "Net-(U$3-RFMIN)") (class "Default")
      (node (ref "RF_MAX") (pin "2") (pinfunction "2_2") (pintype "passive"))
      (node (ref "RF_MIN") (pin "2") (pinfunction "2_2") (pintype "passive"))
      (node (ref "R_SS") (pin "2") (pinfunction "2_2") (pintype "passive"))
      (node (ref "U$3") (pin "4") (pinfunction "RFMIN_4") (pintype "bidirectional"))
    )
    (net (code "108") (name "Net-(U$3-VBOOT)") (class "Default")
      (node (ref "C_BOOT") (pin "1") (pinfunction "1_1") (pintype "passive"))
      (node (ref "U$3") (pin "16") (pinfunction "VBOOT_16") (pintype "bidirectional"))
    )
    (net (code "109") (name "Net-(U$5-ANODE)") (class "Default")
      (node (ref "R14") (pin "2") (pinfunction "2_2") (pintype "passive"))
      (node (ref "U$5") (pin "2") (pinfunction "ANODE_2") (pintype "bidirectional"))
    )
    (net (code "110") (name "Net-(U$6-ANODE)") (class "Default")
      (node (ref "R17") (pin "1") (pinfunction "1_1") (pintype "passive"))
      (node (ref "U$6") (pin "2") (pinfunction "ANODE_2") (pintype "bidirectional"))
    )
    (net (code "111") (name "Net-(U3-CB)") (class "Default")
      (node (ref "C19") (pin "1") (pinfunction "1_1") (pintype "passive"))
      (node (ref "U3") (pin "1") (pinfunction "CB_1") (pintype "input"))
    )
    (net (code "112") (name "Net-(U4-CB)") (class "Default")
      (node (ref "C22") (pin "1") (pinfunction "1_1") (pintype "passive"))
      (node (ref "U4") (pin "1") (pinfunction "CB_1") (pintype "input"))
    )
    (net (code "113") (name "Net-(VR1-C)") (class "Default")
      (node (ref "LED1") (pin "C") (pinfunction "C_C") (pintype "passive"))
      (node (ref "VR1") (pin "1") (pinfunction "C_1") (pintype "passive"))
    )
    (net (code "114") (name "Net-(VR1-R)") (class "Default")
      (node (ref "R33") (pin "1") (pinfunction "1_1") (pintype "passive"))
      (node (ref "R36") (pin "2") (pinfunction "2_2") (pintype "passive"))
      (node (ref "VR1") (pin "2") (pinfunction "R_2") (pintype "passive"))
    )
    (net (code "115") (name "Net-(VR2-C)") (class "Default")
      (node (ref "LED2") (pin "C") (pinfunction "C_C") (pintype "passive"))
      (node (ref "VR2") (pin "1") (pinfunction "C_1") (pintype "passive"))
    )
    (net (code "116") (name "Net-(VR2-R)") (class "Default")
      (node (ref "R34") (pin "1") (pinfunction "1_1") (pintype "passive"))
      (node (ref "R37") (pin "2") (pinfunction "2_2") (pintype "passive"))
      (node (ref "VR2") (pin "2") (pinfunction "R_2") (pintype "passive"))
    )
    (net (code "117") (name "Net-(VR3-C)") (class "Default")
      (node (ref "LED3") (pin "C") (pinfunction "C_C") (pintype "passive"))
      (node (ref "VR3") (pin "1") (pinfunction "C_1") (pintype "passive"))
    )
    (net (code "118") (name "Net-(VR3-R)") (class "Default")
      (node (ref "R35") (pin "1") (pinfunction "1_1") (pintype "passive"))
      (node (ref "R38") (pin "2") (pinfunction "2_2") (pintype "passive"))
      (node (ref "VR3") (pin "2") (pinfunction "R_2") (pintype "passive"))
    )
    (net (code "119") (name "Net-(X1A-KL)") (class "Default")
      (node (ref "F1") (pin "2") (pinfunction "2_2") (pintype "passive"))
      (node (ref "R59") (pin "2") (pinfunction "2_2") (pintype "passive"))
      (node (ref "X1") (pin "1") (pinfunction "KL_1") (pintype "passive"))
    )
    (net (code "120") (name "OC0A{slash}MOSI_A") (class "Default")
      (node (ref "JP4") (pin "1") (pinfunction "1_1") (pintype "passive"))
      (node (ref "SV1") (pin "1") (pinfunction "1_1") (pintype "passive"))
      (node (ref "U$2") (pin "2") (pinfunction "(MOSI_A/TXD)PD3_2") (pintype "bidirectional"))
    )
    (net (code "121") (name "OC1A_FREQ{slash}MISO_A") (class "Default")
      (node (ref "R48") (pin "1") (pinfunction "1_1") (pintype "passive"))
      (node (ref "SV1") (pin "9") (pinfunction "9_9") (pintype "passive"))
      (node (ref "U$2") (pin "1") (pinfunction "(MISO_A)PD2_1") (pintype "bidirectional"))
    )
    (net (code "122") (name "RESET_NOTAUS") (class "Default")
      (node (ref "IC2") (pin "11") (pinfunction "R2_11") (pintype "input"))
      (node (ref "IC2") (pin "15") (pinfunction "R3_15") (pintype "input"))
      (node (ref "U$2") (pin "24") (pinfunction "PB4_24") (pintype "bidirectional"))
    )
    (net (code "123") (name "RST") (class "Default")
      (node (ref "SV1") (pin "5") (pinfunction "5_5") (pintype "passive"))
      (node (ref "U$2") (pin "31") (pinfunction "PE0(RESET)_31") (pintype "input"))
    )
    (net (code "124") (name "RST_ETH") (class "Default")
      (node (ref "U$2") (pin "32") (pinfunction "PD1_32") (pintype "bidirectional"))
      (node (ref "U1") (pin "14") (pinfunction "B6_14") (pintype "bidirectional"))
    )
    (net (code "125") (name "RST_ETH_3V") (class "Default")
      (node (ref "JP2") (pin "3") (pinfunction "3_3") (pintype "passive"))
      (node (ref "U1") (pin "7") (pinfunction "A6_7") (pintype "bidirectional"))
    )
    (net (code "126") (name "SCK") (class "Default")
      (node (ref "U$2") (pin "28") (pinfunction "(SCK)PB7_28") (pintype "bidirectional"))
      (node (ref "U1") (pin "15") (pinfunction "B5_15") (pintype "bidirectional"))
    )
    (net (code "127") (name "SCK_3V") (class "Default")
      (node (ref "JP1") (pin "1") (pinfunction "1_1") (pintype "passive"))
      (node (ref "U1") (pin "6") (pinfunction "A5_6") (pintype "bidirectional"))
    )
    (net (code "128") (name "SERVO_PWM") (class "Default")
      (node (ref "JP3") (pin "1") (pinfunction "1_1") (pintype "passive"))
      (node (ref "U$2") (pin "3") (pinfunction "PC1_3") (pintype "bidirectional"))
    )
    (net (code "129") (name "STBY") (class "Default")
      (node (ref "C12") (pin "1") (pinfunction "1_1") (pintype "passive"))
      (node (ref "R57") (pin "2") (pinfunction "2_2") (pintype "passive"))
      (node (ref "U$3") (pin "5") (pinfunction "STBY_5") (pintype "bidirectional"))
      (node (ref "U2") (pin "3") (pinfunction "2Y_3") (pintype "output"))
    )
    (net (code "130") (name "TASTER") (class "Default")
      (node (ref "C33") (pin "1") (pinfunction "1_1") (pintype "passive"))
      (node (ref "IC2") (pin "14") (pinfunction "S3_14") (pintype "input"))
      (node (ref "R22") (pin "2") (pinfunction "2_2") (pintype "passive"))
      (node (ref "S1") (pin "3") (pinfunction "P_3") (pintype "passive"))
      (node (ref "S1") (pin "4") (pinfunction "P1_4") (pintype "passive"))
    )
    (net (code "131") (name "WOL_ETH") (class "Default")
      (node (ref "U1") (pin "18") (pinfunction "B2_18") (pintype "bidirectional"))
    )
    (net (code "132") (name "WOL_ETH_3V") (class "Default")
      (node (ref "JP1") (pin "4") (pinfunction "4_4") (pintype "passive"))
      (node (ref "U1") (pin "3") (pinfunction "A2_3") (pintype "bidirectional"))
    )
    (net (code "133") (name "unconnected-(IC2A-Q0-Pad2)") (class "Default")
      (node (ref "IC2") (pin "2") (pinfunction "Q0_2") (pintype "output"))
    )
    (net (code "134") (name "unconnected-(IC2A-Q1-Pad9)") (class "Default")
      (node (ref "IC2") (pin "9") (pinfunction "Q1_9") (pintype "output"))
    )
    (net (code "135") (name "unconnected-(IC4B-OUT-Pad7)") (class "Default")
      (node (ref "IC4") (pin "7") (pinfunction "OUT_7") (pintype "output"))
    )
    (net (code "136") (name "unconnected-(L7-2-Pad8)") (class "Default")
      (node (ref "L7") (pin "8") (pinfunction "2_8") (pintype "passive"))
    )
    (net (code "137") (name "unconnected-(L7-3-Pad10)") (class "Default")
      (node (ref "L7") (pin "10") (pinfunction "3_10") (pintype "passive"))
    )
    (net (code "138") (name "unconnected-(L7-7-Pad5)") (class "Default")
      (node (ref "L7") (pin "5") (pinfunction "7_5") (pintype "passive"))
    )
    (net (code "139") (name "unconnected-(L7-Pad6)") (class "Default")
      (node (ref "L7") (pin "6") (pinfunction "6_6") (pintype "passive"))
    )
    (net (code "140") (name "unconnected-(OK2B-A-Pad3)") (class "Default")
      (node (ref "OK2") (pin "3") (pinfunction "A_3") (pintype "passive"))
    )
    (net (code "141") (name "unconnected-(OK2B-C-Pad4)") (class "Default")
      (node (ref "OK2") (pin "4") (pinfunction "C_4") (pintype "passive"))
    )
    (net (code "142") (name "unconnected-(OK2B-COL-Pad6)") (class "Default")
      (node (ref "OK2") (pin "6") (pinfunction "COL_6") (pintype "passive"))
    )
    (net (code "143") (name "unconnected-(OK2B-EMIT-Pad5)") (class "Default")
      (node (ref "OK2") (pin "5") (pinfunction "EMIT_5") (pintype "passive"))
    )
    (net (code "144") (name "unconnected-(RJ_1-PadP$1)") (class "Default")
      (node (ref "RJ_1") (pin "P$1") (pinfunction "P$1_P$1") (pintype "bidirectional"))
    )
    (net (code "145") (name "unconnected-(RJ_2-PadP$1)") (class "Default")
      (node (ref "RJ_2") (pin "P$1") (pinfunction "P$1_P$1") (pintype "bidirectional"))
    )
    (net (code "146") (name "unconnected-(SV1-Pad3)") (class "Default")
      (node (ref "SV1") (pin "3") (pinfunction "3_3") (pintype "passive"))
    )
    (net (code "147") (name "unconnected-(U$1-VREF-Pad5)") (class "Default")
      (node (ref "U$1") (pin "5") (pinfunction "VREF_5") (pintype "output"))
    )
    (net (code "148") (name "unconnected-(U$3-NC-Pad13)") (class "Default")
      (node (ref "U$3") (pin "13") (pinfunction "NC_13") (pintype "bidirectional"))
    )
    (net (code "149") (name "unconnected-(U$3-PFC_STOP-Pad9)") (class "Default")
      (node (ref "U$3") (pin "9") (pinfunction "PFC_STOP_9") (pintype "bidirectional"))
    )
    (net (code "150") (name "unconnected-(U$4-0V-Pad5)") (class "Default")
      (node (ref "U$4") (pin "5") (pinfunction "0V_5") (pintype "bidirectional"))
    )
    (net (code "151") (name "unconnected-(U3-NC-Pad3)") (class "Default")
      (node (ref "U3") (pin "3") (pinfunction "NC_3") (pintype "no_connect"))
    )
    (net (code "152") (name "unconnected-(U3-NC_2-Pad2)") (class "Default")
      (node (ref "U3") (pin "2") (pinfunction "NC_2_2") (pintype "no_connect"))
    )
    (net (code "153") (name "unconnected-(U3-ON{slash}~{OFF}-Pad5)") (class "Default")
      (node (ref "U3") (pin "5") (pinfunction "ON/~{OFF}_5") (pintype "input"))
    )
    (net (code "154") (name "unconnected-(U4-NC-Pad3)") (class "Default")
      (node (ref "U4") (pin "3") (pinfunction "NC_3") (pintype "no_connect"))
    )
    (net (code "155") (name "unconnected-(U4-NC_2-Pad2)") (class "Default")
      (node (ref "U4") (pin "2") (pinfunction "NC_2_2") (pintype "no_connect"))
    )
    (net (code "156") (name "unconnected-(U4-ON{slash}~{OFF}-Pad5)") (class "Default")
      (node (ref "U4") (pin "5") (pinfunction "ON/~{OFF}_5") (pintype "input"))
    )
    (net (code "157") (name "ÜBERSPANNUNG") (class "Default")
      (node (ref "C24") (pin "1") (pinfunction "1_1") (pintype "passive"))
      (node (ref "C41") (pin "1") (pinfunction "1_1") (pintype "passive"))
      (node (ref "IC2") (pin "12") (pinfunction "S2_12") (pintype "input"))
      (node (ref "OK2") (pin "7") (pinfunction "EMIT_7") (pintype "passive"))
      (node (ref "R10") (pin "2") (pinfunction "2_2") (pintype "passive"))
    )
  )
)
